# working.net
KiCad netlist of a schematic drawn in EAGLE
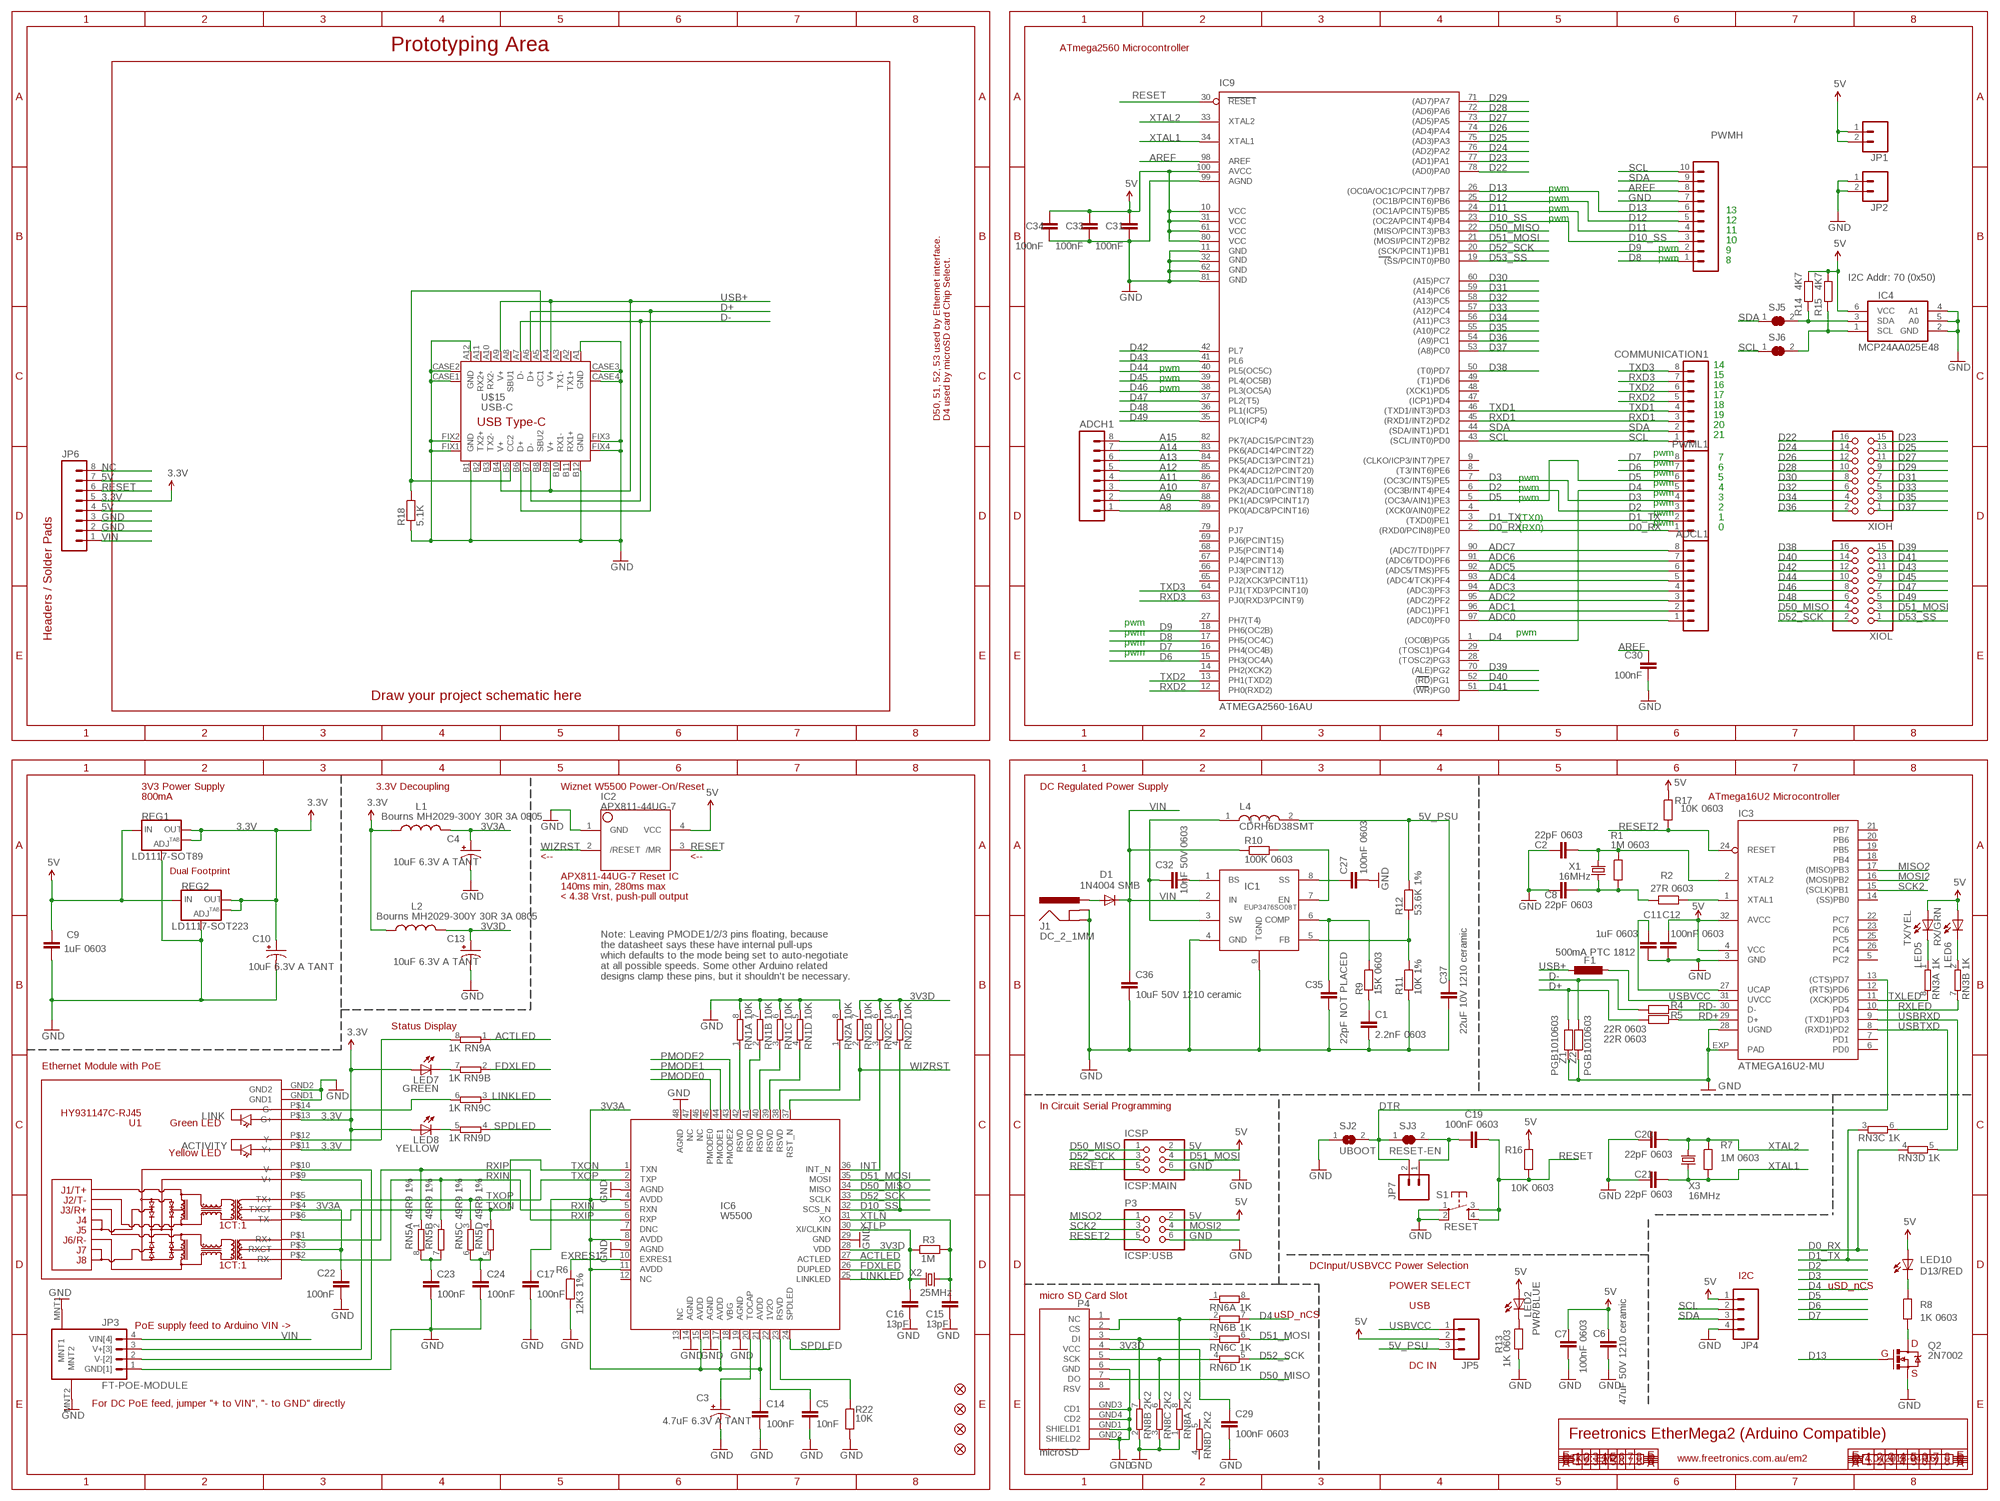
[diagram p0: schematic, sheet 1]

(export (version "E")
  (design (tool "Eeschema 10.0.6"))
  (components
    (comp (ref "ADCH1")
      (value "M08STD")
      (footprint "eagle-import:1X08")
      (libsource (lib "eagle-import") (part "M08STD"))
    )
    (comp (ref "ADCL1")
      (value "M08STD")
      (footprint "eagle-import:1X08")
      (libsource (lib "eagle-import") (part "M08STD"))
    )
    (comp (ref "C1")
      (value "2.2nF 0603")
      (footprint "eagle-import:0603")
      (libsource (lib "eagle-import") (part "freetronics-marc_CAP0603"))
    )
    (comp (ref "C2")
      (value "22pF 0603")
      (footprint "eagle-import:0603")
      (libsource (lib "eagle-import") (part "freetronics-marc_CAP0603"))
    )
    (comp (ref "C3")
      (value "4.7uF 6.3V A TANT")
      (footprint "eagle-import:EIA3216")
      (libsource (lib "eagle-import") (part "CAP_POL1206"))
    )
    (comp (ref "C4")
      (value "10uF 6.3V A TANT")
      (footprint "eagle-import:EIA3216")
      (libsource (lib "eagle-import") (part "CAP_POL1206"))
    )
    (comp (ref "C5")
      (value "10nF")
      (footprint "eagle-import:0603")
      (libsource (lib "eagle-import") (part "CAP0603"))
    )
    (comp (ref "C6")
      (value "47uF 50V 1210 ceramic")
      (footprint "eagle-import:C1210")
      (libsource (lib "eagle-import") (part "C-EUC1210"))
    )
    (comp (ref "C7")
      (value "100nF 0603")
      (footprint "eagle-import:0603")
      (libsource (lib "eagle-import") (part "freetronics-marc_CAP0603"))
    )
    (comp (ref "C8")
      (value "22pF 0603")
      (footprint "eagle-import:0603")
      (libsource (lib "eagle-import") (part "freetronics-marc_CAP0603"))
    )
    (comp (ref "C9")
      (value "1uF 0603")
      (footprint "eagle-import:0603")
      (libsource (lib "eagle-import") (part "freetronics-marc_CAP0603"))
    )
    (comp (ref "C10")
      (value "10uF 6.3V A TANT")
      (footprint "eagle-import:EIA3216")
      (libsource (lib "eagle-import") (part "CAP_POL1206"))
    )
    (comp (ref "C11")
      (value "1uF 0603")
      (footprint "eagle-import:0603")
      (libsource (lib "eagle-import") (part "freetronics-master-v1_CAP0603"))
    )
    (comp (ref "C12")
      (value "100nF 0603")
      (footprint "eagle-import:0603")
      (libsource (lib "eagle-import") (part "freetronics-marc_CAP0603"))
    )
    (comp (ref "C13")
      (value "10uF 6.3V A TANT")
      (footprint "eagle-import:EIA3216")
      (libsource (lib "eagle-import") (part "CAP_POL1206"))
    )
    (comp (ref "C14")
      (value "100nF")
      (footprint "eagle-import:0603")
      (libsource (lib "eagle-import") (part "CAP0603"))
    )
    (comp (ref "C15")
      (value "13pF")
      (footprint "eagle-import:0603")
      (libsource (lib "eagle-import") (part "freetronics-marc_CAP0603"))
    )
    (comp (ref "C16")
      (value "13pF")
      (footprint "eagle-import:0603")
      (libsource (lib "eagle-import") (part "freetronics-marc_CAP0603"))
    )
    (comp (ref "C17")
      (value "100nF")
      (footprint "eagle-import:0603")
      (libsource (lib "eagle-import") (part "CAP0603"))
    )
    (comp (ref "C19")
      (value "100nF 0603")
      (footprint "eagle-import:0603")
      (libsource (lib "eagle-import") (part "freetronics-marc_CAP0603"))
    )
    (comp (ref "C20")
      (value "22pF 0603")
      (footprint "eagle-import:0603")
      (libsource (lib "eagle-import") (part "freetronics-marc_CAP0603"))
    )
    (comp (ref "C21")
      (value "22pF 0603")
      (footprint "eagle-import:0603")
      (libsource (lib "eagle-import") (part "freetronics-marc_CAP0603"))
    )
    (comp (ref "C22")
      (value "100nF")
      (footprint "eagle-import:0603")
      (libsource (lib "eagle-import") (part "freetronics-marc_CAP0603"))
    )
    (comp (ref "C23")
      (value "100nF")
      (footprint "eagle-import:0603")
      (libsource (lib "eagle-import") (part "freetronics-marc_CAP0603"))
    )
    (comp (ref "C24")
      (value "100nF")
      (footprint "eagle-import:0603")
      (libsource (lib "eagle-import") (part "freetronics-marc_CAP0603"))
    )
    (comp (ref "C27")
      (value "100nF 0603")
      (footprint "eagle-import:0603")
      (libsource (lib "eagle-import") (part "freetronics-marc_CAP0603"))
    )
    (comp (ref "C29")
      (value "100nF 0603")
      (footprint "eagle-import:0603")
      (libsource (lib "eagle-import") (part "freetronics-marc_CAP0603"))
    )
    (comp (ref "C30")
      (value "100nF")
      (footprint "eagle-import:0603")
      (libsource (lib "eagle-import") (part "freetronics-marc_CAP0603"))
    )
    (comp (ref "C31")
      (value "100nF")
      (footprint "eagle-import:0603")
      (libsource (lib "eagle-import") (part "freetronics-marc_CAP0603"))
    )
    (comp (ref "C32")
      (value "10nF 50V 0603")
      (footprint "eagle-import:0603")
      (libsource (lib "eagle-import") (part "freetronics-marc_CAP0603"))
    )
    (comp (ref "C33")
      (value "100nF")
      (footprint "eagle-import:0603")
      (libsource (lib "eagle-import") (part "freetronics-marc_CAP0603"))
    )
    (comp (ref "C34")
      (value "100nF")
      (footprint "eagle-import:0603")
      (libsource (lib "eagle-import") (part "freetronics-marc_CAP0603"))
    )
    (comp (ref "C35")
      (value "22pF NOT PLACED")
      (footprint "eagle-import:0603")
      (libsource (lib "eagle-import") (part "freetronics-marc_CAP0603"))
    )
    (comp (ref "C36")
      (value "10uF 50V 1210 ceramic")
      (footprint "eagle-import:C1210")
      (libsource (lib "eagle-import") (part "C-EUC1210"))
    )
    (comp (ref "C37")
      (value "22uF 10V 1210 ceramic")
      (footprint "eagle-import:C1210")
      (libsource (lib "eagle-import") (part "C-EUC1210"))
    )
    (comp (ref "COMMUNICATION1")
      (value "M08STD")
      (footprint "eagle-import:1X08")
      (libsource (lib "eagle-import") (part "M08STD"))
    )
    (comp (ref "D1")
      (value "1N4004 SMB")
      (footprint "eagle-import:SMB-DIODE")
      (libsource (lib "eagle-import") (part "DIODESMB"))
    )
    (comp (ref "F1")
      (value "500mA PTC 1812")
      (footprint "eagle-import:L1812")
      (libsource (lib "eagle-import") (part "L-EUL1812"))
    )
    (comp (ref "FID1")
      (value "FIDUCIAL1X2.5")
      (footprint "eagle-import:FIDUCIAL-1X2.5")
      (libsource (lib "eagle-import") (part "FIDUCIAL1X2.5"))
    )
    (comp (ref "FID2")
      (value "FIDUCIAL1X2.5")
      (footprint "eagle-import:FIDUCIAL-1X2.5")
      (libsource (lib "eagle-import") (part "FIDUCIAL1X2.5"))
    )
    (comp (ref "FID3")
      (value "FIDUCIAL1X2.5")
      (footprint "eagle-import:FIDUCIAL-1X2.5")
      (libsource (lib "eagle-import") (part "FIDUCIAL1X2.5"))
    )
    (comp (ref "FID4")
      (value "FIDUCIAL1X2.5")
      (footprint "eagle-import:FIDUCIAL-1X2.5")
      (libsource (lib "eagle-import") (part "FIDUCIAL1X2.5"))
    )
    (comp (ref "IC1")
      (value "EUP3476SO08T")
      (footprint "eagle-import:SO08T")
      (libsource (lib "eagle-import") (part "EUP3476SO08T"))
    )
    (comp (ref "IC2")
      (value "APX811-44UG-7")
      (footprint "eagle-import:SOT143-R")
      (libsource (lib "eagle-import") (part "APX81X-RESET-IC"))
    )
    (comp (ref "IC3")
      (value "ATMEGA16U2-MU")
      (footprint "eagle-import:ATMEL_QFN32")
      (libsource (lib "eagle-import") (part "ATMEL_ATMEGA8U2-MUQFN"))
    )
    (comp (ref "IC4")
      (value "MCP24AA025E48")
      (footprint "eagle-import:SOT23-6")
      (libsource (lib "eagle-import") (part "MCP24AA025E48"))
    )
    (comp (ref "IC6")
      (value "W5500")
      (footprint "eagle-import:W5500")
      (libsource (lib "eagle-import") (part "W5500"))
    )
    (comp (ref "IC9")
      (value "ATMEGA2560-16AU")
      (footprint "eagle-import:TQFP100")
      (libsource (lib "eagle-import") (part "ATMEGAAU1280-16"))
    )
    (comp (ref "ICSP")
      (value "ICSP:MAIN")
      (footprint "eagle-import:2X03")
      (libsource (lib "eagle-import") (part "PINHD-2X3"))
    )
    (comp (ref "J1")
      (value "DC_2_1MM")
      (footprint "eagle-import:POWER_JACK_PTH_SLOTS")
      (libsource (lib "eagle-import") (part "POWER_JACKPTH_SLOTS"))
    )
    (comp (ref "JP1")
      (value "M02PTH")
      (footprint "eagle-import:1X02")
      (libsource (lib "eagle-import") (part "M02PTH"))
    )
    (comp (ref "JP2")
      (value "M02PTH")
      (footprint "eagle-import:1X02")
      (libsource (lib "eagle-import") (part "M02PTH"))
    )
    (comp (ref "JP3")
      (value "FT-POE-MODULE")
      (footprint "eagle-import:FT-POE-MODULE-CLEAN")
      (libsource (lib "eagle-import") (part "FT-POE-MODULE2"))
    )
    (comp (ref "JP4")
      (value "M04PTH")
      (footprint "eagle-import:1X04")
      (libsource (lib "eagle-import") (part "M04PTH"))
    )
    (comp (ref "JP5")
      (value "M03PTH")
      (footprint "eagle-import:1X03")
      (libsource (lib "eagle-import") (part "M03PTH"))
    )
    (comp (ref "JP6")
      (value "M08STD")
      (footprint "eagle-import:1X08")
      (libsource (lib "eagle-import") (part "M08STD"))
    )
    (comp (ref "JP7")
      (value "M02PTH")
      (footprint "eagle-import:1X02")
      (libsource (lib "eagle-import") (part "freetronics-master-v1.1_M02PTH"))
    )
    (comp (ref "L1")
      (value "Bourns MH2029-300Y 30R 3A 0805")
      (footprint "eagle-import:L2012C")
      (libsource (lib "eagle-import") (part "L-USL2012C"))
    )
    (comp (ref "L2")
      (value "Bourns MH2029-300Y 30R 3A 0805")
      (footprint "eagle-import:L2012C")
      (libsource (lib "eagle-import") (part "L-USL2012C"))
    )
    (comp (ref "L4")
      (value "CDRH6D38SMT")
      (footprint "eagle-import:CDRH")
      (libsource (lib "eagle-import") (part "CDRH6D38SMT"))
    )
    (comp (ref "LED2")
      (value "PWR/BLUE")
      (footprint "eagle-import:LED-0603")
      (libsource (lib "eagle-import") (part "LED0603"))
    )
    (comp (ref "LED5")
      (value "TX/YEL")
      (footprint "eagle-import:LED-0603")
      (libsource (lib "eagle-import") (part "LED0603"))
    )
    (comp (ref "LED6")
      (value "RX/GRN")
      (footprint "eagle-import:LED-0603")
      (libsource (lib "eagle-import") (part "LED0603"))
    )
    (comp (ref "LED7")
      (value "GREEN")
      (footprint "eagle-import:LED-0603")
      (libsource (lib "eagle-import") (part "LED0603"))
    )
    (comp (ref "LED8")
      (value "YELLOW")
      (footprint "eagle-import:LED-0603")
      (libsource (lib "eagle-import") (part "LED0603"))
    )
    (comp (ref "LED10")
      (value "D13/RED")
      (footprint "eagle-import:LED-0603")
      (libsource (lib "eagle-import") (part "LED0603"))
    )
    (comp (ref "P3")
      (value "ICSP:USB")
      (footprint "eagle-import:2X03")
      (libsource (lib "eagle-import") (part "PINHD-2X3"))
    )
    (comp (ref "P4")
      (value "microSD")
      (footprint "eagle-import:MOLEX-SD-500901-003")
      (libsource (lib "eagle-import") (part "USD-SOCKETHINGE"))
    )
    (comp (ref "PWMH")
      (value "M100.1")
      (footprint "eagle-import:1X10")
      (libsource (lib "eagle-import") (part "M100.1"))
    )
    (comp (ref "PWML1")
      (value "M08STD")
      (footprint "eagle-import:1X08")
      (libsource (lib "eagle-import") (part "M08STD"))
    )
    (comp (ref "Q2")
      (value "2N7002")
      (footprint "eagle-import:SOT23-3")
      (libsource (lib "eagle-import") (part "MOSFET-NCHANNELSMD"))
    )
    (comp (ref "R1")
      (value "1M 0603")
      (footprint "eagle-import:0603")
      (libsource (lib "eagle-import") (part "freetronics-marc_RESISTOR0603"))
    )
    (comp (ref "R2")
      (value "27R 0603")
      (footprint "eagle-import:0603")
      (libsource (lib "eagle-import") (part "freetronics-marc_RESISTOR0603"))
    )
    (comp (ref "R3")
      (value "1M")
      (footprint "eagle-import:0603")
      (libsource (lib "eagle-import") (part "freetronics-marc_RESISTOR0603"))
    )
    (comp (ref "R4")
      (value "22R 0603")
      (footprint "eagle-import:0603")
      (libsource (lib "eagle-import") (part "freetronics-marc_RESISTOR0603"))
    )
    (comp (ref "R5")
      (value "22R 0603")
      (footprint "eagle-import:0603")
      (libsource (lib "eagle-import") (part "freetronics-marc_RESISTOR0603"))
    )
    (comp (ref "R6")
      (value "12K3 1%")
      (footprint "eagle-import:0603")
      (libsource (lib "eagle-import") (part "freetronics-marc_RESISTOR0603"))
    )
    (comp (ref "R7")
      (value "1M 0603")
      (footprint "eagle-import:0603")
      (libsource (lib "eagle-import") (part "freetronics-marc_RESISTOR0603"))
    )
    (comp (ref "R8")
      (value "1K 0603")
      (footprint "eagle-import:0603")
      (libsource (lib "eagle-import") (part "freetronics-marc_RESISTOR0603"))
    )
    (comp (ref "R9")
      (value "15K 0603")
      (footprint "eagle-import:0603")
      (libsource (lib "eagle-import") (part "freetronics-original_RESISTOR0603"))
    )
    (comp (ref "R10")
      (value "100K 0603")
      (footprint "eagle-import:0603")
      (libsource (lib "eagle-import") (part "freetronics-original_RESISTOR0603"))
    )
    (comp (ref "R11")
      (value "10K 1%")
      (footprint "eagle-import:0603")
      (libsource (lib "eagle-import") (part "freetronics-original_RESISTOR0603"))
    )
    (comp (ref "R12")
      (value "53.6K 1%")
      (footprint "eagle-import:0603")
      (libsource (lib "eagle-import") (part "freetronics-original_RESISTOR0603"))
    )
    (comp (ref "R13")
      (value "1K 0603")
      (footprint "eagle-import:0603")
      (libsource (lib "eagle-import") (part "freetronics-marc_RESISTOR0603"))
    )
    (comp (ref "R14")
      (value "4K7")
      (footprint "eagle-import:0603")
      (libsource (lib "eagle-import") (part "freetronics-master-v1.1_RESISTOR0603"))
    )
    (comp (ref "R15")
      (value "4K7")
      (footprint "eagle-import:0603")
      (libsource (lib "eagle-import") (part "freetronics-master-v1.1_RESISTOR0603"))
    )
    (comp (ref "R16")
      (value "10K 0603")
      (footprint "eagle-import:0603")
      (libsource (lib "eagle-import") (part "freetronics-marc_RESISTOR0603"))
    )
    (comp (ref "R17")
      (value "10K 0603")
      (footprint "eagle-import:0603")
      (libsource (lib "eagle-import") (part "freetronics-marc_RESISTOR0603"))
    )
    (comp (ref "R18")
      (value "5.1K")
      (footprint "eagle-import:0603")
      (libsource (lib "eagle-import") (part "freetronics-original_RESISTOR0603"))
    )
    (comp (ref "R22")
      (value "10K")
      (footprint "eagle-import:0603")
      (libsource (lib "eagle-import") (part "freetronics-marc_RESISTOR0603"))
    )
    (comp (ref "REG1")
      (value "LD1117-SOT89")
      (footprint "eagle-import:SOT89")
      (libsource (lib "eagle-import") (part "V_REG_LM1117SOT89"))
    )
    (comp (ref "REG2")
      (value "LD1117-SOT223")
      (footprint "eagle-import:SOT223")
      (libsource (lib "eagle-import") (part "V_REG_LM1117SOT223"))
    )
    (comp (ref "RN1")
      (value "10K")
      (footprint "eagle-import:CAY16")
      (libsource (lib "eagle-import") (part "freetronics-master-v1.1_4R-NCAY16"))
    )
    (comp (ref "RN2")
      (value "10K")
      (footprint "eagle-import:CAY16")
      (libsource (lib "eagle-import") (part "freetronics-master-v1.1_4R-NCAY16"))
    )
    (comp (ref "RN3")
      (value "1K")
      (footprint "eagle-import:CAY16")
      (libsource (lib "eagle-import") (part "4R-NCAY16"))
    )
    (comp (ref "RN5")
      (value "49R9 1%")
      (footprint "eagle-import:CAY16")
      (libsource (lib "eagle-import") (part "4R-NCAY16"))
    )
    (comp (ref "RN6")
      (value "1K")
      (footprint "eagle-import:CAY16")
      (libsource (lib "eagle-import") (part "4R-NCAY16"))
    )
    (comp (ref "RN8")
      (value "2K2")
      (footprint "eagle-import:CAY16")
      (libsource (lib "eagle-import") (part "4R-NCAY16"))
    )
    (comp (ref "RN9")
      (value "1K")
      (footprint "eagle-import:CAY16")
      (libsource (lib "eagle-import") (part "freetronics-master-v1.1_4R-NCAY16"))
    )
    (comp (ref "S1")
      (value "RESET")
      (footprint "eagle-import:TACTILE_SWITCH_SMD")
      (libsource (lib "eagle-import") (part "TAC_SWITCHSMD"))
    )
    (comp (ref "SJ2")
      (value "UBOOT")
      (footprint "eagle-import:SJ")
      (libsource (lib "eagle-import") (part "SJ"))
    )
    (comp (ref "SJ3")
      (value "RESET-EN")
      (footprint "eagle-import:SJC")
      (libsource (lib "eagle-import") (part "SJCN"))
    )
    (comp (ref "SJ5")
      (value "SJCN")
      (footprint "eagle-import:SJC")
      (libsource (lib "eagle-import") (part "SJCN"))
    )
    (comp (ref "SJ6")
      (value "SJCN")
      (footprint "eagle-import:SJC")
      (libsource (lib "eagle-import") (part "SJCN"))
    )
    (comp (ref "U$15")
      (value "USB-C")
      (footprint "eagle-import:USB-C-U52A")
      (libsource (lib "eagle-import") (part "USB-C"))
    )
    (comp (ref "U1")
      (value "HY931147C-RJ45")
      (footprint "eagle-import:HY931147C")
      (libsource (lib "eagle-import") (part "HY931147C-RJ45"))
    )
    (comp (ref "X1")
      (value "16MHz")
      (footprint "eagle-import:HC49U-V")
      (libsource (lib "eagle-import") (part "CRYSTALHC49UV"))
    )
    (comp (ref "X2")
      (value "25MHz")
      (footprint "eagle-import:HC49U-V")
      (libsource (lib "eagle-import") (part "CRYSTALHC49UV"))
    )
    (comp (ref "X3")
      (value "16MHz")
      (footprint "eagle-import:HC49U-V")
      (libsource (lib "eagle-import") (part "CRYSTALHC49UV"))
    )
    (comp (ref "XIOH")
      (value "PINHD-2X8")
      (footprint "eagle-import:2X08")
      (libsource (lib "eagle-import") (part "PINHD-2X8"))
    )
    (comp (ref "XIOL")
      (value "PINHD-2X8")
      (footprint "eagle-import:2X08")
      (libsource (lib "eagle-import") (part "PINHD-2X8"))
    )
    (comp (ref "Z1")
      (value "PGB1010603")
      (footprint "eagle-import:0603")
      (libsource (lib "eagle-import") (part "RESISTOR0603"))
    )
    (comp (ref "Z2")
      (value "PGB1010603")
      (footprint "eagle-import:0603")
      (libsource (lib "eagle-import") (part "RESISTOR0603"))
    )
  )
  (nets
    (net (code "1") (name "/3V3A") (class "Default")
      (node (ref "C14") (pin "1") (pinfunction "1_1") (pintype "passive"))
      (node (ref "C17") (pin "1") (pinfunction "1_1") (pintype "passive"))
      (node (ref "C22") (pin "1") (pinfunction "1_1") (pintype "passive"))
      (node (ref "C4") (pin "A") (pinfunction "+_A") (pintype "passive"))
      (node (ref "IC6") (pin "11") (pinfunction "AVDD_11") (pintype "passive"))
      (node (ref "IC6") (pin "15") (pinfunction "AVDD_15") (pintype "passive"))
      (node (ref "IC6") (pin "17") (pinfunction "AVDD_17") (pintype "passive"))
      (node (ref "IC6") (pin "21") (pinfunction "AVDD_21") (pintype "passive"))
      (node (ref "IC6") (pin "4") (pinfunction "AVDD_4") (pintype "passive"))
      (node (ref "IC6") (pin "8") (pinfunction "AVDD_8") (pintype "passive"))
      (node (ref "L1") (pin "2") (pinfunction "2_2") (pintype "passive"))
      (node (ref "U1") (pin "P$3") (pinfunction "RXCT_P$3") (pintype "bidirectional"))
      (node (ref "U1") (pin "P$4") (pinfunction "TXCT_P$4") (pintype "bidirectional"))
    )
    (net (code "2") (name "/3V3D") (class "Default")
      (node (ref "C13") (pin "A") (pinfunction "+_A") (pintype "passive"))
      (node (ref "C29") (pin "1") (pinfunction "1_1") (pintype "passive"))
      (node (ref "IC6") (pin "28") (pinfunction "VDD_28") (pintype "passive"))
      (node (ref "L2") (pin "2") (pinfunction "2_2") (pintype "passive"))
      (node (ref "P4") (pin "4") (pinfunction "VCC_4") (pintype "bidirectional"))
      (node (ref "RN2") (pin "5") (pinfunction "2_5") (pintype "passive"))
      (node (ref "RN2") (pin "6") (pinfunction "2_6") (pintype "passive"))
      (node (ref "RN2") (pin "7") (pinfunction "2_7") (pintype "passive"))
    )
    (net (code "3") (name "/5V_PSU") (class "Default")
      (node (ref "C37") (pin "1") (pinfunction "1_1") (pintype "passive"))
      (node (ref "JP5") (pin "3") (pinfunction "3_3") (pintype "passive"))
      (node (ref "L4") (pin "2") (pinfunction "2_2") (pintype "bidirectional"))
      (node (ref "R12") (pin "2") (pinfunction "2_2") (pintype "passive"))
    )
    (net (code "4") (name "/A8") (class "Default")
      (node (ref "ADCH1") (pin "1") (pinfunction "1_1") (pintype "passive"))
      (node (ref "IC9") (pin "89") (pinfunction "PK0(ADC8/PCINT16)_89") (pintype "bidirectional"))
    )
    (net (code "5") (name "/A9") (class "Default")
      (node (ref "ADCH1") (pin "2") (pinfunction "2_2") (pintype "passive"))
      (node (ref "IC9") (pin "88") (pinfunction "PK1(ADC9/PCINT17)_88") (pintype "bidirectional"))
    )
    (net (code "6") (name "/A10") (class "Default")
      (node (ref "ADCH1") (pin "3") (pinfunction "3_3") (pintype "passive"))
      (node (ref "IC9") (pin "87") (pinfunction "PK2(ADC10/PCINT18)_87") (pintype "bidirectional"))
    )
    (net (code "7") (name "/A11") (class "Default")
      (node (ref "ADCH1") (pin "4") (pinfunction "4_4") (pintype "passive"))
      (node (ref "IC9") (pin "86") (pinfunction "PK3(ADC11/PCINT19)_86") (pintype "bidirectional"))
    )
    (net (code "8") (name "/A12") (class "Default")
      (node (ref "ADCH1") (pin "5") (pinfunction "5_5") (pintype "passive"))
      (node (ref "IC9") (pin "85") (pinfunction "PK4(ADC12/PCINT20)_85") (pintype "bidirectional"))
    )
    (net (code "9") (name "/A13") (class "Default")
      (node (ref "ADCH1") (pin "6") (pinfunction "6_6") (pintype "passive"))
      (node (ref "IC9") (pin "84") (pinfunction "PK5(ADC13/PCINT21)_84") (pintype "bidirectional"))
    )
    (net (code "10") (name "/A14") (class "Default")
      (node (ref "ADCH1") (pin "7") (pinfunction "7_7") (pintype "passive"))
      (node (ref "IC9") (pin "83") (pinfunction "PK6(ADC14/PCINT22)_83") (pintype "bidirectional"))
    )
    (net (code "11") (name "/A15") (class "Default")
      (node (ref "ADCH1") (pin "8") (pinfunction "8_8") (pintype "passive"))
      (node (ref "IC9") (pin "82") (pinfunction "PK7(ADC15/PCINT23)_82") (pintype "bidirectional"))
    )
    (net (code "12") (name "/ACTLED") (class "Default")
      (node (ref "IC6") (pin "27") (pinfunction "ACTLED_27") (pintype "passive"))
      (node (ref "RN9") (pin "1") (pinfunction "1_1") (pintype "passive"))
    )
    (net (code "13") (name "/ADC0") (class "Default")
      (node (ref "ADCL1") (pin "1") (pinfunction "1_1") (pintype "passive"))
      (node (ref "IC9") (pin "97") (pinfunction "(ADC0)PF0_97") (pintype "bidirectional"))
    )
    (net (code "14") (name "/ADC1") (class "Default")
      (node (ref "ADCL1") (pin "2") (pinfunction "2_2") (pintype "passive"))
      (node (ref "IC9") (pin "96") (pinfunction "(ADC1)PF1_96") (pintype "bidirectional"))
    )
    (net (code "15") (name "/ADC2") (class "Default")
      (node (ref "ADCL1") (pin "3") (pinfunction "3_3") (pintype "passive"))
      (node (ref "IC9") (pin "95") (pinfunction "(ADC2)PF2_95") (pintype "bidirectional"))
    )
    (net (code "16") (name "/ADC3") (class "Default")
      (node (ref "ADCL1") (pin "4") (pinfunction "4_4") (pintype "passive"))
      (node (ref "IC9") (pin "94") (pinfunction "(ADC3)PF3_94") (pintype "bidirectional"))
    )
    (net (code "17") (name "/ADC4") (class "Default")
      (node (ref "ADCL1") (pin "5") (pinfunction "5_5") (pintype "passive"))
      (node (ref "IC9") (pin "93") (pinfunction "(ADC4/TCK)PF4_93") (pintype "bidirectional"))
    )
    (net (code "18") (name "/ADC5") (class "Default")
      (node (ref "ADCL1") (pin "6") (pinfunction "6_6") (pintype "passive"))
      (node (ref "IC9") (pin "92") (pinfunction "(ADC5/TMS)PF5_92") (pintype "bidirectional"))
    )
    (net (code "19") (name "/ADC6") (class "Default")
      (node (ref "ADCL1") (pin "7") (pinfunction "7_7") (pintype "passive"))
      (node (ref "IC9") (pin "91") (pinfunction "(ADC6/TDO)PF6_91") (pintype "bidirectional"))
    )
    (net (code "20") (name "/ADC7") (class "Default")
      (node (ref "ADCL1") (pin "8") (pinfunction "8_8") (pintype "passive"))
      (node (ref "IC9") (pin "90") (pinfunction "(ADC7/TDI)PF7_90") (pintype "bidirectional"))
    )
    (net (code "21") (name "/AREF") (class "Default")
      (node (ref "C30") (pin "1") (pinfunction "1_1") (pintype "passive"))
      (node (ref "IC9") (pin "98") (pinfunction "AREF_98") (pintype "bidirectional"))
      (node (ref "PWMH") (pin "8") (pinfunction "8_8") (pintype "passive"))
    )
    (net (code "22") (name "/D+") (class "Default")
      (node (ref "R5") (pin "2") (pinfunction "2_2") (pintype "passive"))
      (node (ref "U$15") (pin "A6") (pinfunction "D+_A6") (pintype "bidirectional"))
      (node (ref "U$15") (pin "B6") (pinfunction "D+_B6") (pintype "bidirectional"))
      (node (ref "Z1") (pin "1") (pinfunction "1_1") (pintype "passive"))
    )
    (net (code "23") (name "/D-") (class "Default")
      (node (ref "R4") (pin "2") (pinfunction "2_2") (pintype "passive"))
      (node (ref "U$15") (pin "A7") (pinfunction "D-_A7") (pintype "bidirectional"))
      (node (ref "U$15") (pin "B7") (pinfunction "D-_B7") (pintype "bidirectional"))
      (node (ref "Z2") (pin "1") (pinfunction "1_1") (pintype "passive"))
    )
    (net (code "24") (name "/D0_RX") (class "Default")
      (node (ref "IC9") (pin "2") (pinfunction "(RXD0/PCIN8)PE0_2") (pintype "bidirectional"))
      (node (ref "PWML1") (pin "1") (pinfunction "1_1") (pintype "passive"))
      (node (ref "RN3") (pin "4") (pinfunction "1_4") (pintype "passive"))
    )
    (net (code "25") (name "/D1_TX") (class "Default")
      (node (ref "IC9") (pin "3") (pinfunction "(TXD0)PE1_3") (pintype "bidirectional"))
      (node (ref "PWML1") (pin "2") (pinfunction "2_2") (pintype "passive"))
      (node (ref "RN3") (pin "3") (pinfunction "1_3") (pintype "passive"))
    )
    (net (code "26") (name "/D2") (class "Default")
      (node (ref "IC9") (pin "6") (pinfunction "(OC3B/INT4)PE4_6") (pintype "bidirectional"))
      (node (ref "PWML1") (pin "3") (pinfunction "3_3") (pintype "passive"))
    )
    (net (code "27") (name "/D3") (class "Default")
      (node (ref "IC9") (pin "7") (pinfunction "(OC3C/INT5)PE5_7") (pintype "bidirectional"))
      (node (ref "PWML1") (pin "4") (pinfunction "4_4") (pintype "passive"))
    )
    (net (code "28") (name "/D4") (class "Default")
      (node (ref "IC9") (pin "1") (pinfunction "(OC0B)PG5_1") (pintype "bidirectional"))
      (node (ref "PWML1") (pin "5") (pinfunction "5_5") (pintype "passive"))
      (node (ref "RN6") (pin "7") (pinfunction "2_7") (pintype "passive"))
    )
    (net (code "29") (name "/D5") (class "Default")
      (node (ref "IC9") (pin "5") (pinfunction "(OC3A/AIN1)PE3_5") (pintype "bidirectional"))
      (node (ref "PWML1") (pin "6") (pinfunction "6_6") (pintype "passive"))
    )
    (net (code "30") (name "/D6") (class "Default")
      (node (ref "IC9") (pin "15") (pinfunction "PH3(OC4A)_15") (pintype "bidirectional"))
      (node (ref "PWML1") (pin "7") (pinfunction "7_7") (pintype "passive"))
    )
    (net (code "31") (name "/D7") (class "Default")
      (node (ref "IC9") (pin "16") (pinfunction "PH4(OC4B)_16") (pintype "bidirectional"))
      (node (ref "PWML1") (pin "8") (pinfunction "8_8") (pintype "passive"))
    )
    (net (code "32") (name "/D8") (class "Default")
      (node (ref "IC9") (pin "17") (pinfunction "PH5(OC4C)_17") (pintype "bidirectional"))
      (node (ref "PWMH") (pin "1") (pinfunction "1_1") (pintype "passive"))
    )
    (net (code "33") (name "/D9") (class "Default")
      (node (ref "IC9") (pin "18") (pinfunction "PH6(OC2B)_18") (pintype "bidirectional"))
      (node (ref "PWMH") (pin "2") (pinfunction "2_2") (pintype "passive"))
    )
    (net (code "34") (name "/D10_SS") (class "Default")
      (node (ref "IC6") (pin "32") (pinfunction "SCS_N_32") (pintype "passive"))
      (node (ref "IC9") (pin "23") (pinfunction "(OC2A/PCINT4)PB4_23") (pintype "bidirectional"))
      (node (ref "PWMH") (pin "3") (pinfunction "3_3") (pintype "passive"))
      (node (ref "RN2") (pin "4") (pinfunction "1_4") (pintype "passive"))
    )
    (net (code "35") (name "/D11") (class "Default")
      (node (ref "IC9") (pin "24") (pinfunction "(OC1A/PCINT5)PB5_24") (pintype "bidirectional"))
      (node (ref "PWMH") (pin "4") (pinfunction "4_4") (pintype "passive"))
    )
    (net (code "36") (name "/D12") (class "Default")
      (node (ref "IC9") (pin "25") (pinfunction "(OC1B/PCINT6)PB6_25") (pintype "bidirectional"))
      (node (ref "PWMH") (pin "5") (pinfunction "5_5") (pintype "passive"))
    )
    (net (code "37") (name "/D13") (class "Default")
      (node (ref "IC9") (pin "26") (pinfunction "(OC0A/OC1C/PCINT7)PB7_26") (pintype "bidirectional"))
      (node (ref "PWMH") (pin "6") (pinfunction "6_6") (pintype "passive"))
      (node (ref "Q2") (pin "1") (pinfunction "G_1") (pintype "passive"))
    )
    (net (code "38") (name "/D22") (class "Default")
      (node (ref "IC9") (pin "78") (pinfunction "(AD0)PA0_78") (pintype "bidirectional"))
      (node (ref "XIOH") (pin "16") (pinfunction "16_16") (pintype "passive"))
    )
    (net (code "39") (name "/D23") (class "Default")
      (node (ref "IC9") (pin "77") (pinfunction "(AD1)PA1_77") (pintype "bidirectional"))
      (node (ref "XIOH") (pin "15") (pinfunction "15_15") (pintype "passive"))
    )
    (net (code "40") (name "/D24") (class "Default")
      (node (ref "IC9") (pin "76") (pinfunction "(AD2)PA2_76") (pintype "bidirectional"))
      (node (ref "XIOH") (pin "14") (pinfunction "14_14") (pintype "passive"))
    )
    (net (code "41") (name "/D25") (class "Default")
      (node (ref "IC9") (pin "75") (pinfunction "(AD3)PA3_75") (pintype "bidirectional"))
      (node (ref "XIOH") (pin "13") (pinfunction "13_13") (pintype "passive"))
    )
    (net (code "42") (name "/D26") (class "Default")
      (node (ref "IC9") (pin "74") (pinfunction "(AD4)PA4_74") (pintype "bidirectional"))
      (node (ref "XIOH") (pin "12") (pinfunction "12_12") (pintype "passive"))
    )
    (net (code "43") (name "/D27") (class "Default")
      (node (ref "IC9") (pin "73") (pinfunction "(AD5)PA5_73") (pintype "bidirectional"))
      (node (ref "XIOH") (pin "11") (pinfunction "11_11") (pintype "passive"))
    )
    (net (code "44") (name "/D28") (class "Default")
      (node (ref "IC9") (pin "72") (pinfunction "(AD6)PA6_72") (pintype "bidirectional"))
      (node (ref "XIOH") (pin "10") (pinfunction "10_10") (pintype "passive"))
    )
    (net (code "45") (name "/D29") (class "Default")
      (node (ref "IC9") (pin "71") (pinfunction "(AD7)PA7_71") (pintype "bidirectional"))
      (node (ref "XIOH") (pin "9") (pinfunction "9_9") (pintype "passive"))
    )
    (net (code "46") (name "/D30") (class "Default")
      (node (ref "IC9") (pin "60") (pinfunction "(A15)PC7_60") (pintype "bidirectional"))
      (node (ref "XIOH") (pin "8") (pinfunction "8_8") (pintype "passive"))
    )
    (net (code "47") (name "/D31") (class "Default")
      (node (ref "IC9") (pin "59") (pinfunction "(A14)PC6_59") (pintype "bidirectional"))
      (node (ref "XIOH") (pin "7") (pinfunction "7_7") (pintype "passive"))
    )
    (net (code "48") (name "/D32") (class "Default")
      (node (ref "IC9") (pin "58") (pinfunction "(A13)PC5_58") (pintype "bidirectional"))
      (node (ref "XIOH") (pin "6") (pinfunction "6_6") (pintype "passive"))
    )
    (net (code "49") (name "/D33") (class "Default")
      (node (ref "IC9") (pin "57") (pinfunction "(A12)PC4_57") (pintype "bidirectional"))
      (node (ref "XIOH") (pin "5") (pinfunction "5_5") (pintype "passive"))
    )
    (net (code "50") (name "/D34") (class "Default")
      (node (ref "IC9") (pin "56") (pinfunction "(A11)PC3_56") (pintype "bidirectional"))
      (node (ref "XIOH") (pin "4") (pinfunction "4_4") (pintype "passive"))
    )
    (net (code "51") (name "/D35") (class "Default")
      (node (ref "IC9") (pin "55") (pinfunction "(A10)PC2_55") (pintype "bidirectional"))
      (node (ref "XIOH") (pin "3") (pinfunction "3_3") (pintype "passive"))
    )
    (net (code "52") (name "/D36") (class "Default")
      (node (ref "IC9") (pin "54") (pinfunction "(A9)PC1_54") (pintype "bidirectional"))
      (node (ref "XIOH") (pin "2") (pinfunction "2_2") (pintype "passive"))
    )
    (net (code "53") (name "/D37") (class "Default")
      (node (ref "IC9") (pin "53") (pinfunction "(A8)PC0_53") (pintype "bidirectional"))
      (node (ref "XIOH") (pin "1") (pinfunction "1_1") (pintype "passive"))
    )
    (net (code "54") (name "/D38") (class "Default")
      (node (ref "IC9") (pin "50") (pinfunction "(T0)PD7_50") (pintype "bidirectional"))
      (node (ref "XIOL") (pin "16") (pinfunction "16_16") (pintype "passive"))
    )
    (net (code "55") (name "/D39") (class "Default")
      (node (ref "IC9") (pin "70") (pinfunction "(ALE)PG2_70") (pintype "bidirectional"))
      (node (ref "XIOL") (pin "15") (pinfunction "15_15") (pintype "passive"))
    )
    (net (code "56") (name "/D40") (class "Default")
      (node (ref "IC9") (pin "52") (pinfunction "(RD)PG1_52") (pintype "bidirectional"))
      (node (ref "XIOL") (pin "14") (pinfunction "14_14") (pintype "passive"))
    )
    (net (code "57") (name "/D41") (class "Default")
      (node (ref "IC9") (pin "51") (pinfunction "(WR)PG0_51") (pintype "bidirectional"))
      (node (ref "XIOL") (pin "13") (pinfunction "13_13") (pintype "passive"))
    )
    (net (code "58") (name "/D42") (class "Default")
      (node (ref "IC9") (pin "42") (pinfunction "PL7_42") (pintype "bidirectional"))
      (node (ref "XIOL") (pin "12") (pinfunction "12_12") (pintype "passive"))
    )
    (net (code "59") (name "/D43") (class "Default")
      (node (ref "IC9") (pin "41") (pinfunction "PL6_41") (pintype "bidirectional"))
      (node (ref "XIOL") (pin "11") (pinfunction "11_11") (pintype "passive"))
    )
    (net (code "60") (name "/D44") (class "Default")
      (node (ref "IC9") (pin "40") (pinfunction "PL5(OC5C)_40") (pintype "bidirectional"))
      (node (ref "XIOL") (pin "10") (pinfunction "10_10") (pintype "passive"))
    )
    (net (code "61") (name "/D45") (class "Default")
      (node (ref "IC9") (pin "39") (pinfunction "PL4(OC5B)_39") (pintype "bidirectional"))
      (node (ref "XIOL") (pin "9") (pinfunction "9_9") (pintype "passive"))
    )
    (net (code "62") (name "/D46") (class "Default")
      (node (ref "IC9") (pin "38") (pinfunction "PL3(OC5A)_38") (pintype "bidirectional"))
      (node (ref "XIOL") (pin "8") (pinfunction "8_8") (pintype "passive"))
    )
    (net (code "63") (name "/D47") (class "Default")
      (node (ref "IC9") (pin "37") (pinfunction "PL2(T5)_37") (pintype "bidirectional"))
      (node (ref "XIOL") (pin "7") (pinfunction "7_7") (pintype "passive"))
    )
    (net (code "64") (name "/D48") (class "Default")
      (node (ref "IC9") (pin "36") (pinfunction "PL1(ICP5)_36") (pintype "bidirectional"))
      (node (ref "XIOL") (pin "6") (pinfunction "6_6") (pintype "passive"))
    )
    (net (code "65") (name "/D49") (class "Default")
      (node (ref "IC9") (pin "35") (pinfunction "PL0(ICP4)_35") (pintype "bidirectional"))
      (node (ref "XIOL") (pin "5") (pinfunction "5_5") (pintype "passive"))
    )
    (net (code "66") (name "/D50_MISO") (class "Default")
      (node (ref "IC6") (pin "34") (pinfunction "MISO_34") (pintype "passive"))
      (node (ref "IC9") (pin "22") (pinfunction "(MISO/PCINT3)PB3_22") (pintype "bidirectional"))
      (node (ref "ICSP") (pin "1") (pinfunction "1_1") (pintype "passive"))
      (node (ref "P4") (pin "7") (pinfunction "DO_7") (pintype "bidirectional"))
      (node (ref "XIOL") (pin "4") (pinfunction "4_4") (pintype "passive"))
    )
    (net (code "67") (name "/D51_MOSI") (class "Default")
      (node (ref "IC6") (pin "35") (pinfunction "MOSI_35") (pintype "passive"))
      (node (ref "IC9") (pin "21") (pinfunction "(MOSI/PCINT2)PB2_21") (pintype "bidirectional"))
      (node (ref "ICSP") (pin "4") (pinfunction "4_4") (pintype "passive"))
      (node (ref "RN6") (pin "6") (pinfunction "2_6") (pintype "passive"))
      (node (ref "XIOL") (pin "3") (pinfunction "3_3") (pintype "passive"))
    )
    (net (code "68") (name "/D52_SCK") (class "Default")
      (node (ref "IC6") (pin "33") (pinfunction "SCLK_33") (pintype "passive"))
      (node (ref "IC9") (pin "20") (pinfunction "(SCK/PCINT1)PB1_20") (pintype "bidirectional"))
      (node (ref "ICSP") (pin "3") (pinfunction "3_3") (pintype "passive"))
      (node (ref "RN6") (pin "5") (pinfunction "2_5") (pintype "passive"))
      (node (ref "XIOL") (pin "2") (pinfunction "2_2") (pintype "passive"))
    )
    (net (code "69") (name "/D53_SS") (class "Default")
      (node (ref "IC9") (pin "19") (pinfunction "(SS/PCINT0)PB0_19") (pintype "bidirectional"))
      (node (ref "XIOL") (pin "1") (pinfunction "1_1") (pintype "passive"))
    )
    (net (code "70") (name "/DTR") (class "Default")
      (node (ref "IC3") (pin "13") (pinfunction "(CTS)PD7_13") (pintype "bidirectional"))
      (node (ref "JP7") (pin "2") (pinfunction "2_2") (pintype "passive"))
      (node (ref "SJ2") (pin "2") (pinfunction "2_2") (pintype "passive"))
      (node (ref "SJ3") (pin "1") (pinfunction "1_1") (pintype "passive"))
    )
    (net (code "71") (name "/EXRES1") (class "Default")
      (node (ref "IC6") (pin "10") (pinfunction "EXRES1_10") (pintype "passive"))
      (node (ref "R6") (pin "2") (pinfunction "2_2") (pintype "passive"))
    )
    (net (code "72") (name "/FDXLED") (class "Default")
      (node (ref "IC6") (pin "26") (pinfunction "DUPLED_26") (pintype "passive"))
      (node (ref "RN9") (pin "2") (pinfunction "1_2") (pintype "passive"))
    )
    (net (code "73") (name "/INT") (class "Default")
      (node (ref "IC6") (pin "36") (pinfunction "INT_N_36") (pintype "passive"))
      (node (ref "RN2") (pin "3") (pinfunction "1_3") (pintype "passive"))
    )
    (net (code "74") (name "/LINKLED") (class "Default")
      (node (ref "IC6") (pin "25") (pinfunction "LINKLED_25") (pintype "passive"))
      (node (ref "RN9") (pin "3") (pinfunction "1_3") (pintype "passive"))
    )
    (net (code "75") (name "/MISO2") (class "Default")
      (node (ref "IC3") (pin "17") (pinfunction "(MISO)PB3_17") (pintype "bidirectional"))
      (node (ref "P3") (pin "1") (pinfunction "1_1") (pintype "passive"))
    )
    (net (code "76") (name "/MOSI2") (class "Default")
      (node (ref "IC3") (pin "16") (pinfunction "(MOSI)PB2_16") (pintype "bidirectional"))
      (node (ref "P3") (pin "4") (pinfunction "4_4") (pintype "passive"))
    )
    (net (code "77") (name "/NC") (class "Default")
      (node (ref "JP6") (pin "8") (pinfunction "8_8") (pintype "passive"))
    )
    (net (code "78") (name "/PMODE0") (class "Default")
      (node (ref "IC6") (pin "45") (pinfunction "PMODE0_45") (pintype "passive"))
    )
    (net (code "79") (name "/PMODE1") (class "Default")
      (node (ref "IC6") (pin "44") (pinfunction "PMODE1_44") (pintype "passive"))
    )
    (net (code "80") (name "/PMODE2") (class "Default")
      (node (ref "IC6") (pin "43") (pinfunction "PMODE2_43") (pintype "passive"))
    )
    (net (code "81") (name "/RD+") (class "Default")
      (node (ref "IC3") (pin "29") (pinfunction "D+_29") (pintype "bidirectional"))
      (node (ref "R5") (pin "1") (pinfunction "1_1") (pintype "passive"))
    )
    (net (code "82") (name "/RD-") (class "Default")
      (node (ref "IC3") (pin "30") (pinfunction "D-_30") (pintype "bidirectional"))
      (node (ref "R4") (pin "1") (pinfunction "1_1") (pintype "passive"))
    )
    (net (code "83") (name "/RESET") (class "Default")
      (node (ref "C19") (pin "2") (pinfunction "2_2") (pintype "passive"))
      (node (ref "IC2") (pin "3") (pinfunction "/MR_3") (pintype "input"))
      (node (ref "IC9") (pin "30") (pinfunction "RESET_30") (pintype "input"))
      (node (ref "ICSP") (pin "5") (pinfunction "5_5") (pintype "passive"))
      (node (ref "JP6") (pin "6") (pinfunction "6_6") (pintype "passive"))
      (node (ref "R16") (pin "1") (pinfunction "1_1") (pintype "passive"))
      (node (ref "S1") (pin "3") (pinfunction "3_3") (pintype "passive"))
      (node (ref "S1") (pin "4") (pinfunction "4_4") (pintype "passive"))
    )
    (net (code "84") (name "/RESET2") (class "Default")
      (node (ref "IC3") (pin "24") (pinfunction "RESET_24") (pintype "input"))
      (node (ref "P3") (pin "5") (pinfunction "5_5") (pintype "passive"))
      (node (ref "R17") (pin "1") (pinfunction "1_1") (pintype "passive"))
    )
    (net (code "85") (name "/RXD1") (class "Default")
      (node (ref "COMMUNICATION1") (pin "3") (pinfunction "3_3") (pintype "passive"))
      (node (ref "IC9") (pin "45") (pinfunction "(RXD1/INT2)PD2_45") (pintype "bidirectional"))
    )
    (net (code "86") (name "/RXD2") (class "Default")
      (node (ref "COMMUNICATION1") (pin "5") (pinfunction "5_5") (pintype "passive"))
      (node (ref "IC9") (pin "12") (pinfunction "PH0(RXD2)_12") (pintype "bidirectional"))
    )
    (net (code "87") (name "/RXD3") (class "Default")
      (node (ref "COMMUNICATION1") (pin "7") (pinfunction "7_7") (pintype "passive"))
      (node (ref "IC9") (pin "63") (pinfunction "PJ0(RXD3/PCINT9)_63") (pintype "bidirectional"))
    )
    (net (code "88") (name "/RXIN") (class "Default")
      (node (ref "IC6") (pin "5") (pinfunction "RXN_5") (pintype "passive"))
      (node (ref "RN5") (pin "2") (pinfunction "1_2") (pintype "passive"))
      (node (ref "U1") (pin "P$2") (pinfunction "RX-_P$2") (pintype "bidirectional"))
    )
    (net (code "89") (name "/RXIP") (class "Default")
      (node (ref "IC6") (pin "6") (pinfunction "RXP_6") (pintype "passive"))
      (node (ref "RN5") (pin "1") (pinfunction "1_1") (pintype "passive"))
      (node (ref "U1") (pin "P$1") (pinfunction "RX+_P$1") (pintype "bidirectional"))
    )
    (net (code "90") (name "/RXLED") (class "Default")
      (node (ref "IC3") (pin "10") (pinfunction "PD4_10") (pintype "bidirectional"))
      (node (ref "RN3") (pin "7") (pinfunction "2_7") (pintype "passive"))
    )
    (net (code "91") (name "/SCK2") (class "Default")
      (node (ref "IC3") (pin "15") (pinfunction "(SCLK)PB1_15") (pintype "bidirectional"))
      (node (ref "P3") (pin "3") (pinfunction "3_3") (pintype "passive"))
    )
    (net (code "92") (name "/SCL") (class "Default")
      (node (ref "COMMUNICATION1") (pin "1") (pinfunction "1_1") (pintype "passive"))
      (node (ref "IC9") (pin "43") (pinfunction "(SCL/INT0)PD0_43") (pintype "bidirectional"))
      (node (ref "JP4") (pin "2") (pinfunction "2_2") (pintype "passive"))
      (node (ref "PWMH") (pin "10") (pinfunction "10_10") (pintype "passive"))
      (node (ref "SJ6") (pin "1") (pinfunction "1_1") (pintype "passive"))
    )
    (net (code "93") (name "/SDA") (class "Default")
      (node (ref "COMMUNICATION1") (pin "2") (pinfunction "2_2") (pintype "passive"))
      (node (ref "IC9") (pin "44") (pinfunction "(SDA/INT1)PD1_44") (pintype "bidirectional"))
      (node (ref "JP4") (pin "3") (pinfunction "3_3") (pintype "passive"))
      (node (ref "PWMH") (pin "9") (pinfunction "9_9") (pintype "passive"))
      (node (ref "SJ5") (pin "1") (pinfunction "1_1") (pintype "passive"))
    )
    (net (code "94") (name "/SPDLED") (class "Default")
      (node (ref "IC6") (pin "24") (pinfunction "SPDLED_24") (pintype "passive"))
      (node (ref "RN9") (pin "4") (pinfunction "1_4") (pintype "passive"))
    )
    (net (code "95") (name "/TXD1") (class "Default")
      (node (ref "COMMUNICATION1") (pin "4") (pinfunction "4_4") (pintype "passive"))
      (node (ref "IC9") (pin "46") (pinfunction "(TXD1/INT3)PD3_46") (pintype "bidirectional"))
    )
    (net (code "96") (name "/TXD2") (class "Default")
      (node (ref "COMMUNICATION1") (pin "6") (pinfunction "6_6") (pintype "passive"))
      (node (ref "IC9") (pin "13") (pinfunction "PH1(TXD2)_13") (pintype "bidirectional"))
    )
    (net (code "97") (name "/TXD3") (class "Default")
      (node (ref "COMMUNICATION1") (pin "8") (pinfunction "8_8") (pintype "passive"))
      (node (ref "IC9") (pin "64") (pinfunction "PJ1(TXD3/PCINT10)_64") (pintype "bidirectional"))
    )
    (net (code "98") (name "/TXLED") (class "Default")
      (node (ref "IC3") (pin "11") (pinfunction "(XCK)PD5_11") (pintype "bidirectional"))
      (node (ref "RN3") (pin "8") (pinfunction "2_8") (pintype "passive"))
    )
    (net (code "99") (name "/TXON") (class "Default")
      (node (ref "IC6") (pin "1") (pinfunction "TXN_1") (pintype "passive"))
      (node (ref "RN5") (pin "4") (pinfunction "1_4") (pintype "passive"))
      (node (ref "U1") (pin "P$6") (pinfunction "TX-_P$6") (pintype "bidirectional"))
    )
    (net (code "100") (name "/TXOP") (class "Default")
      (node (ref "IC6") (pin "2") (pinfunction "TXP_2") (pintype "passive"))
      (node (ref "RN5") (pin "3") (pinfunction "1_3") (pintype "passive"))
      (node (ref "U1") (pin "P$5") (pinfunction "TX+_P$5") (pintype "bidirectional"))
    )
    (net (code "101") (name "/USB+") (class "Default")
      (node (ref "F1") (pin "1") (pinfunction "1_1") (pintype "passive"))
      (node (ref "U$15") (pin "A4") (pinfunction "V+_A4") (pintype "power_in"))
      (node (ref "U$15") (pin "A9") (pinfunction "V+_A9") (pintype "power_in"))
      (node (ref "U$15") (pin "B4") (pinfunction "V+_B4") (pintype "power_in"))
      (node (ref "U$15") (pin "B9") (pinfunction "V+_B9") (pintype "power_in"))
    )
    (net (code "102") (name "/USBRXD") (class "Default")
      (node (ref "IC3") (pin "9") (pinfunction "(TXD1)PD3_9") (pintype "bidirectional"))
      (node (ref "RN3") (pin "5") (pinfunction "2_5") (pintype "passive"))
    )
    (net (code "103") (name "/USBTXD") (class "Default")
      (node (ref "IC3") (pin "8") (pinfunction "(RXD1)PD2_8") (pintype "bidirectional"))
      (node (ref "RN3") (pin "6") (pinfunction "2_6") (pintype "passive"))
    )
    (net (code "104") (name "/USBVCC") (class "Default")
      (node (ref "F1") (pin "2") (pinfunction "2_2") (pintype "passive"))
      (node (ref "IC3") (pin "31") (pinfunction "UVCC_31") (pintype "power_in"))
      (node (ref "JP5") (pin "1") (pinfunction "1_1") (pintype "passive"))
    )
    (net (code "105") (name "/VIN") (class "Default")
      (node (ref "C36") (pin "1") (pinfunction "1_1") (pintype "passive"))
      (node (ref "D1") (pin "C") (pinfunction "C_C") (pintype "passive"))
      (node (ref "IC1") (pin "2") (pinfunction "IN_2") (pintype "power_in"))
      (node (ref "JP3") (pin "4") (pinfunction "VIN[4]_4") (pintype "passive"))
      (node (ref "JP6") (pin "1") (pinfunction "1_1") (pintype "passive"))
      (node (ref "R10") (pin "1") (pinfunction "1_1") (pintype "passive"))
    )
    (net (code "106") (name "/WIZRST") (class "Default")
      (node (ref "IC2") (pin "2") (pinfunction "/RESET_2") (pintype "output"))
      (node (ref "IC6") (pin "37") (pinfunction "RST_N_37") (pintype "passive"))
      (node (ref "RN2") (pin "2") (pinfunction "1_2") (pintype "passive"))
    )
    (net (code "107") (name "/XTAL1") (class "Default")
      (node (ref "C21") (pin "2") (pinfunction "2_2") (pintype "passive"))
      (node (ref "IC9") (pin "34") (pinfunction "XTAL1_34") (pintype "input"))
      (node (ref "R7") (pin "1") (pinfunction "1_1") (pintype "passive"))
      (node (ref "X3") (pin "1") (pinfunction "1_1") (pintype "passive"))
    )
    (net (code "108") (name "/XTAL2") (class "Default")
      (node (ref "C20") (pin "2") (pinfunction "2_2") (pintype "passive"))
      (node (ref "IC9") (pin "33") (pinfunction "XTAL2_33") (pintype "output"))
      (node (ref "R7") (pin "2") (pinfunction "2_2") (pintype "passive"))
      (node (ref "X3") (pin "2") (pinfunction "2_2") (pintype "passive"))
    )
    (net (code "109") (name "/XTLN") (class "Default")
      (node (ref "C15") (pin "1") (pinfunction "1_1") (pintype "passive"))
      (node (ref "IC6") (pin "31") (pinfunction "XO_31") (pintype "passive"))
      (node (ref "R3") (pin "1") (pinfunction "1_1") (pintype "passive"))
      (node (ref "X2") (pin "1") (pinfunction "1_1") (pintype "passive"))
    )
    (net (code "110") (name "/XTLP") (class "Default")
      (node (ref "C16") (pin "1") (pinfunction "1_1") (pintype "passive"))
      (node (ref "IC6") (pin "30") (pinfunction "XI/CLKIN_30") (pintype "passive"))
      (node (ref "R3") (pin "2") (pinfunction "2_2") (pintype "passive"))
      (node (ref "X2") (pin "2") (pinfunction "2_2") (pintype "passive"))
    )
    (net (code "111") (name "3.3V") (class "Default")
      (node (ref "C10") (pin "A") (pinfunction "+_A") (pintype "passive"))
      (node (ref "JP6") (pin "5") (pinfunction "5_5") (pintype "passive"))
      (node (ref "L1") (pin "1") (pinfunction "1_1") (pintype "passive"))
      (node (ref "L2") (pin "1") (pinfunction "1_1") (pintype "passive"))
      (node (ref "LED7") (pin "A") (pinfunction "A_A") (pintype "passive"))
      (node (ref "LED8") (pin "A") (pinfunction "A_A") (pintype "passive"))
      (node (ref "REG1") (pin "2") (pinfunction "OUT_2") (pintype "output"))
      (node (ref "REG1") (pin "4") (pinfunction "OUT_4") (pintype "output"))
      (node (ref "REG2") (pin "2") (pinfunction "OUT_2") (pintype "output"))
      (node (ref "REG2") (pin "4") (pinfunction "OUT_4") (pintype "output"))
      (node (ref "U1") (pin "P$11") (pinfunction "Y+_P$11") (pintype "bidirectional"))
      (node (ref "U1") (pin "P$13") (pinfunction "G+_P$13") (pintype "bidirectional"))
    )
    (net (code "112") (name "5V") (class "Default")
      (node (ref "C12") (pin "1") (pinfunction "1_1") (pintype "passive"))
      (node (ref "C31") (pin "1") (pinfunction "1_1") (pintype "passive"))
      (node (ref "C33") (pin "1") (pinfunction "1_1") (pintype "passive"))
      (node (ref "C34") (pin "1") (pinfunction "1_1") (pintype "passive"))
      (node (ref "C6") (pin "2") (pinfunction "2_2") (pintype "passive"))
      (node (ref "C7") (pin "1") (pinfunction "1_1") (pintype "passive"))
      (node (ref "C9") (pin "1") (pinfunction "1_1") (pintype "passive"))
      (node (ref "IC2") (pin "4") (pinfunction "VCC_4") (pintype "power_in"))
      (node (ref "IC3") (pin "32") (pinfunction "AVCC_32") (pintype "power_in"))
      (node (ref "IC3") (pin "4") (pinfunction "VCC_4") (pintype "power_in"))
      (node (ref "IC4") (pin "6") (pinfunction "VCC_6") (pintype "power_in"))
      (node (ref "IC9") (pin "10") (pinfunction "VCC_10") (pintype "power_in"))
      (node (ref "IC9") (pin "100") (pinfunction "AVCC_100") (pintype "power_in"))
      (node (ref "IC9") (pin "31") (pinfunction "VCC1_31") (pintype "power_in"))
      (node (ref "IC9") (pin "61") (pinfunction "VCC2_61") (pintype "power_in"))
      (node (ref "IC9") (pin "80") (pinfunction "VCC3_80") (pintype "power_in"))
      (node (ref "ICSP") (pin "2") (pinfunction "2_2") (pintype "passive"))
      (node (ref "JP1") (pin "1") (pinfunction "1_1") (pintype "passive"))
      (node (ref "JP1") (pin "2") (pinfunction "2_2") (pintype "passive"))
      (node (ref "JP4") (pin "1") (pinfunction "1_1") (pintype "passive"))
      (node (ref "JP5") (pin "2") (pinfunction "2_2") (pintype "passive"))
      (node (ref "JP6") (pin "4") (pinfunction "4_4") (pintype "passive"))
      (node (ref "JP6") (pin "7") (pinfunction "7_7") (pintype "passive"))
      (node (ref "LED10") (pin "A") (pinfunction "A_A") (pintype "passive"))
      (node (ref "LED2") (pin "A") (pinfunction "A_A") (pintype "passive"))
      (node (ref "LED5") (pin "A") (pinfunction "A_A") (pintype "passive"))
      (node (ref "LED6") (pin "A") (pinfunction "A_A") (pintype "passive"))
      (node (ref "P3") (pin "2") (pinfunction "2_2") (pintype "passive"))
      (node (ref "R14") (pin "1") (pinfunction "1_1") (pintype "passive"))
      (node (ref "R15") (pin "1") (pinfunction "1_1") (pintype "passive"))
      (node (ref "R16") (pin "2") (pinfunction "2_2") (pintype "passive"))
      (node (ref "R17") (pin "2") (pinfunction "2_2") (pintype "passive"))
      (node (ref "REG1") (pin "3") (pinfunction "IN_3") (pintype "input"))
      (node (ref "REG2") (pin "3") (pinfunction "IN_3") (pintype "input"))
    )
    (net (code "113") (name "GND") (class "Default")
      (node (ref "C1") (pin "2") (pinfunction "2_2") (pintype "passive"))
      (node (ref "C10") (pin "C") (pinfunction "-_C") (pintype "passive"))
      (node (ref "C11") (pin "2") (pinfunction "2_2") (pintype "passive"))
      (node (ref "C12") (pin "2") (pinfunction "2_2") (pintype "passive"))
      (node (ref "C13") (pin "C") (pinfunction "-_C") (pintype "passive"))
      (node (ref "C14") (pin "2") (pinfunction "2_2") (pintype "passive"))
      (node (ref "C15") (pin "2") (pinfunction "2_2") (pintype "passive"))
      (node (ref "C16") (pin "2") (pinfunction "2_2") (pintype "passive"))
      (node (ref "C17") (pin "2") (pinfunction "2_2") (pintype "passive"))
      (node (ref "C2") (pin "1") (pinfunction "1_1") (pintype "passive"))
      (node (ref "C20") (pin "1") (pinfunction "1_1") (pintype "passive"))
      (node (ref "C21") (pin "1") (pinfunction "1_1") (pintype "passive"))
      (node (ref "C22") (pin "2") (pinfunction "2_2") (pintype "passive"))
      (node (ref "C23") (pin "2") (pinfunction "2_2") (pintype "passive"))
      (node (ref "C24") (pin "2") (pinfunction "2_2") (pintype "passive"))
      (node (ref "C27") (pin "2") (pinfunction "2_2") (pintype "passive"))
      (node (ref "C29") (pin "2") (pinfunction "2_2") (pintype "passive"))
      (node (ref "C3") (pin "C") (pinfunction "-_C") (pintype "passive"))
      (node (ref "C30") (pin "2") (pinfunction "2_2") (pintype "passive"))
      (node (ref "C31") (pin "2") (pinfunction "2_2") (pintype "passive"))
      (node (ref "C33") (pin "2") (pinfunction "2_2") (pintype "passive"))
      (node (ref "C34") (pin "2") (pinfunction "2_2") (pintype "passive"))
      (node (ref "C35") (pin "2") (pinfunction "2_2") (pintype "passive"))
      (node (ref "C36") (pin "2") (pinfunction "2_2") (pintype "passive"))
      (node (ref "C37") (pin "2") (pinfunction "2_2") (pintype "passive"))
      (node (ref "C4") (pin "C") (pinfunction "-_C") (pintype "passive"))
      (node (ref "C5") (pin "2") (pinfunction "2_2") (pintype "passive"))
      (node (ref "C6") (pin "1") (pinfunction "1_1") (pintype "passive"))
      (node (ref "C7") (pin "2") (pinfunction "2_2") (pintype "passive"))
      (node (ref "C8") (pin "1") (pinfunction "1_1") (pintype "passive"))
      (node (ref "C9") (pin "2") (pinfunction "2_2") (pintype "passive"))
      (node (ref "IC1") (pin "4") (pinfunction "GND_4") (pintype "power_in"))
      (node (ref "IC1") (pin "9") (pinfunction "TGND_9") (pintype "power_in"))
      (node (ref "IC2") (pin "1") (pinfunction "GND_1") (pintype "power_in"))
      (node (ref "IC3") (pin "28") (pinfunction "UGND_28") (pintype "power_in"))
      (node (ref "IC3") (pin "3") (pinfunction "GND_3") (pintype "power_in"))
      (node (ref "IC3") (pin "EXP") (pinfunction "PAD_EXP") (pintype "power_in"))
      (node (ref "IC4") (pin "2") (pinfunction "GND_2") (pintype "power_in"))
      (node (ref "IC4") (pin "4") (pinfunction "A1_4") (pintype "input"))
      (node (ref "IC4") (pin "5") (pinfunction "A0_5") (pintype "input"))
      (node (ref "IC6") (pin "14") (pinfunction "AGND_14") (pintype "passive"))
      (node (ref "IC6") (pin "16") (pinfunction "AGND_16") (pintype "passive"))
      (node (ref "IC6") (pin "19") (pinfunction "AGND_19") (pintype "passive"))
      (node (ref "IC6") (pin "29") (pinfunction "GND_29") (pintype "passive"))
      (node (ref "IC6") (pin "3") (pinfunction "AGND_3") (pintype "passive"))
      (node (ref "IC6") (pin "48") (pinfunction "AGND_48") (pintype "passive"))
      (node (ref "IC6") (pin "9") (pinfunction "AGND_9") (pintype "passive"))
      (node (ref "IC9") (pin "11") (pinfunction "GND_11") (pintype "power_in"))
      (node (ref "IC9") (pin "32") (pinfunction "GND1_32") (pintype "power_in"))
      (node (ref "IC9") (pin "62") (pinfunction "GND2_62") (pintype "power_in"))
      (node (ref "IC9") (pin "81") (pinfunction "GND3_81") (pintype "power_in"))
      (node (ref "IC9") (pin "99") (pinfunction "AGND_99") (pintype "power_in"))
      (node (ref "ICSP") (pin "6") (pinfunction "6_6") (pintype "passive"))
      (node (ref "J1") (pin "GND") (pinfunction "GND_GND") (pintype "bidirectional"))
      (node (ref "J1") (pin "GNDBREAK") (pinfunction "GNDBREAK_GNDBREAK") (pintype "bidirectional"))
      (node (ref "JP2") (pin "1") (pinfunction "1_1") (pintype "passive"))
      (node (ref "JP2") (pin "2") (pinfunction "2_2") (pintype "passive"))
      (node (ref "JP3") (pin "1") (pinfunction "GND[1]_1") (pintype "passive"))
      (node (ref "JP3") (pin "MNT1") (pinfunction "MNT1_MNT1") (pintype "passive"))
      (node (ref "JP3") (pin "MNT2") (pinfunction "MNT2_MNT2") (pintype "passive"))
      (node (ref "JP4") (pin "4") (pinfunction "4_4") (pintype "passive"))
      (node (ref "JP6") (pin "2") (pinfunction "2_2") (pintype "passive"))
      (node (ref "JP6") (pin "3") (pinfunction "3_3") (pintype "passive"))
      (node (ref "P3") (pin "6") (pinfunction "6_6") (pintype "passive"))
      (node (ref "P4") (pin "6") (pinfunction "GND_6") (pintype "bidirectional"))
      (node (ref "P4") (pin "GND1") (pinfunction "SHIELD1_GND1") (pintype "bidirectional"))
      (node (ref "P4") (pin "GND2") (pinfunction "SHIELD2_GND2") (pintype "bidirectional"))
      (node (ref "P4") (pin "GND3") (pinfunction "CD1_GND3") (pintype "bidirectional"))
      (node (ref "P4") (pin "GND4") (pinfunction "CD2_GND4") (pintype "bidirectional"))
      (node (ref "PWMH") (pin "7") (pinfunction "7_7") (pintype "passive"))
      (node (ref "Q2") (pin "2") (pinfunction "S_2") (pintype "passive"))
      (node (ref "R11") (pin "1") (pinfunction "1_1") (pintype "passive"))
      (node (ref "R13") (pin "1") (pinfunction "1_1") (pintype "passive"))
      (node (ref "R18") (pin "1") (pinfunction "1_1") (pintype "passive"))
      (node (ref "R22") (pin "1") (pinfunction "1_1") (pintype "passive"))
      (node (ref "R6") (pin "1") (pinfunction "1_1") (pintype "passive"))
      (node (ref "REG1") (pin "1") (pinfunction "ADJ_1") (pintype "input"))
      (node (ref "REG2") (pin "1") (pinfunction "ADJ_1") (pintype "input"))
      (node (ref "RN1") (pin "5") (pinfunction "2_5") (pintype "passive"))
      (node (ref "RN1") (pin "6") (pinfunction "2_6") (pintype "passive"))
      (node (ref "RN1") (pin "7") (pinfunction "2_7") (pintype "passive"))
      (node (ref "RN1") (pin "8") (pinfunction "2_8") (pintype "passive"))
      (node (ref "RN2") (pin "8") (pinfunction "2_8") (pintype "passive"))
      (node (ref "RN8") (pin "1") (pinfunction "1_1") (pintype "passive"))
      (node (ref "RN8") (pin "2") (pinfunction "1_2") (pintype "passive"))
      (node (ref "RN8") (pin "3") (pinfunction "1_3") (pintype "passive"))
      (node (ref "S1") (pin "1") (pinfunction "1_1") (pintype "passive"))
      (node (ref "S1") (pin "2") (pinfunction "2_2") (pintype "passive"))
      (node (ref "SJ2") (pin "1") (pinfunction "1_1") (pintype "passive"))
      (node (ref "U$15") (pin "A1") (pinfunction "GND_A1") (pintype "power_in"))
      (node (ref "U$15") (pin "A12") (pinfunction "GND_A12") (pintype "power_in"))
      (node (ref "U$15") (pin "B1") (pinfunction "GND_B1") (pintype "power_in"))
      (node (ref "U$15") (pin "B12") (pinfunction "GND_B12") (pintype "power_in"))
      (node (ref "U$15") (pin "CASE1") (pinfunction "GND_CASE1") (pintype "power_in"))
      (node (ref "U$15") (pin "CASE2") (pinfunction "GND_CASE2") (pintype "power_in"))
      (node (ref "U$15") (pin "CASE3") (pinfunction "GND_CASE3") (pintype "power_in"))
      (node (ref "U$15") (pin "CASE4") (pinfunction "GND_CASE4") (pintype "power_in"))
      (node (ref "U$15") (pin "FIX1") (pinfunction "GND_FIX1") (pintype "power_in"))
      (node (ref "U$15") (pin "FIX2") (pinfunction "GND_FIX2") (pintype "power_in"))
      (node (ref "U$15") (pin "FIX3") (pinfunction "GND_FIX3") (pintype "power_in"))
      (node (ref "U$15") (pin "FIX4") (pinfunction "GND_FIX4") (pintype "power_in"))
      (node (ref "U1") (pin "GND1") (pinfunction "GND1_GND1") (pintype "bidirectional"))
      (node (ref "U1") (pin "GND2") (pinfunction "GND2_GND2") (pintype "bidirectional"))
      (node (ref "Z1") (pin "2") (pinfunction "2_2") (pintype "passive"))
      (node (ref "Z2") (pin "2") (pinfunction "2_2") (pintype "passive"))
    )
    (net (code "114") (name "Net-(C1-Pad1)") (class "Default")
      (node (ref "C1") (pin "1") (pinfunction "1_1") (pintype "passive"))
      (node (ref "R9") (pin "1") (pinfunction "1_1") (pintype "passive"))
    )
    (net (code "115") (name "Net-(C3-+)") (class "Default")
      (node (ref "C3") (pin "A") (pinfunction "+_A") (pintype "passive"))
      (node (ref "IC6") (pin "20") (pinfunction "TOCAP_20") (pintype "passive"))
    )
    (net (code "116") (name "Net-(C8-Pad2)") (class "Default")
      (node (ref "C8") (pin "2") (pinfunction "2_2") (pintype "passive"))
      (node (ref "R1") (pin "1") (pinfunction "1_1") (pintype "passive"))
      (node (ref "R2") (pin "2") (pinfunction "2_2") (pintype "passive"))
      (node (ref "X1") (pin "1") (pinfunction "1_1") (pintype "passive"))
    )
    (net (code "117") (name "Net-(C19-Pad1)") (class "Default")
      (node (ref "C19") (pin "1") (pinfunction "1_1") (pintype "passive"))
      (node (ref "JP7") (pin "1") (pinfunction "1_1") (pintype "passive"))
      (node (ref "SJ3") (pin "2") (pinfunction "2_2") (pintype "passive"))
    )
    (net (code "118") (name "Net-(D1-PadA)") (class "Default")
      (node (ref "D1") (pin "A") (pinfunction "A_A") (pintype "passive"))
      (node (ref "J1") (pin "PWR") (pinfunction "PWR_PWR") (pintype "bidirectional"))
    )
    (net (code "119") (name "Net-(IC1-BS)") (class "Default")
      (node (ref "C32") (pin "2") (pinfunction "2_2") (pintype "passive"))
      (node (ref "IC1") (pin "1") (pinfunction "BS_1") (pintype "bidirectional"))
    )
    (net (code "120") (name "Net-(IC1-COMP)") (class "Default")
      (node (ref "C35") (pin "1") (pinfunction "1_1") (pintype "passive"))
      (node (ref "IC1") (pin "6") (pinfunction "COMP_6") (pintype "bidirectional"))
      (node (ref "R9") (pin "2") (pinfunction "2_2") (pintype "passive"))
    )
    (net (code "121") (name "Net-(IC1-EN)") (class "Default")
      (node (ref "IC1") (pin "7") (pinfunction "EN_7") (pintype "input"))
      (node (ref "R10") (pin "2") (pinfunction "2_2") (pintype "passive"))
    )
    (net (code "122") (name "Net-(IC1-FB)") (class "Default")
      (node (ref "IC1") (pin "5") (pinfunction "FB_5") (pintype "bidirectional"))
      (node (ref "R11") (pin "2") (pinfunction "2_2") (pintype "passive"))
      (node (ref "R12") (pin "1") (pinfunction "1_1") (pintype "passive"))
    )
    (net (code "123") (name "Net-(IC1-SS)") (class "Default")
      (node (ref "C27") (pin "1") (pinfunction "1_1") (pintype "passive"))
      (node (ref "IC1") (pin "8") (pinfunction "SS_8") (pintype "bidirectional"))
    )
    (net (code "124") (name "Net-(IC1-SW)") (class "Default")
      (node (ref "C32") (pin "1") (pinfunction "1_1") (pintype "passive"))
      (node (ref "IC1") (pin "3") (pinfunction "SW_3") (pintype "bidirectional"))
      (node (ref "L4") (pin "1") (pinfunction "1_1") (pintype "bidirectional"))
    )
    (net (code "125") (name "Net-(IC3-UCAP)") (class "Default")
      (node (ref "C11") (pin "1") (pinfunction "1_1") (pintype "passive"))
      (node (ref "IC3") (pin "27") (pinfunction "UCAP_27") (pintype "passive"))
    )
    (net (code "126") (name "Net-(IC3-XTAL1)") (class "Default")
      (node (ref "IC3") (pin "1") (pinfunction "XTAL1_1") (pintype "bidirectional"))
      (node (ref "R2") (pin "1") (pinfunction "1_1") (pintype "passive"))
    )
    (net (code "127") (name "Net-(IC3-XTAL2)") (class "Default")
      (node (ref "C2") (pin "2") (pinfunction "2_2") (pintype "passive"))
      (node (ref "IC3") (pin "2") (pinfunction "XTAL2_2") (pintype "bidirectional"))
      (node (ref "R1") (pin "2") (pinfunction "2_2") (pintype "passive"))
      (node (ref "X1") (pin "2") (pinfunction "2_2") (pintype "passive"))
    )
    (net (code "128") (name "Net-(IC4-SCL)") (class "Default")
      (node (ref "IC4") (pin "1") (pinfunction "SCL_1") (pintype "bidirectional"))
      (node (ref "R15") (pin "2") (pinfunction "2_2") (pintype "passive"))
      (node (ref "SJ6") (pin "2") (pinfunction "2_2") (pintype "passive"))
    )
    (net (code "129") (name "Net-(IC4-SDA)") (class "Default")
      (node (ref "IC4") (pin "3") (pinfunction "SDA_3") (pintype "bidirectional"))
      (node (ref "R14") (pin "2") (pinfunction "2_2") (pintype "passive"))
      (node (ref "SJ5") (pin "2") (pinfunction "2_2") (pintype "passive"))
    )
    (net (code "130") (name "Net-(IC6-1V2O)") (class "Default")
      (node (ref "C5") (pin "1") (pinfunction "1_1") (pintype "passive"))
      (node (ref "IC6") (pin "22") (pinfunction "1V2O_22") (pintype "passive"))
    )
    (net (code "131") (name "Net-(IC6-RSVD-Pad23)") (class "Default")
      (node (ref "IC6") (pin "23") (pinfunction "RSVD_23") (pintype "passive"))
      (node (ref "R22") (pin "2") (pinfunction "2_2") (pintype "passive"))
    )
    (net (code "132") (name "Net-(IC6-RSVD-Pad38)") (class "Default")
      (node (ref "IC6") (pin "38") (pinfunction "RSVD_38") (pintype "passive"))
      (node (ref "RN2") (pin "1") (pinfunction "1_1") (pintype "passive"))
    )
    (net (code "133") (name "Net-(IC6-RSVD-Pad42)") (class "Default")
      (node (ref "IC6") (pin "42") (pinfunction "RSVD_42") (pintype "passive"))
      (node (ref "RN1") (pin "1") (pinfunction "1_1") (pintype "passive"))
    )
    (net (code "134") (name "Net-(JP3-V+[3])") (class "Default")
      (node (ref "JP3") (pin "3") (pinfunction "V+[3]_3") (pintype "passive"))
      (node (ref "U1") (pin "P$9") (pinfunction "V+_P$9") (pintype "bidirectional"))
    )
    (net (code "135") (name "Net-(JP3-V-[2])") (class "Default")
      (node (ref "JP3") (pin "2") (pinfunction "V-[2]_2") (pintype "passive"))
      (node (ref "U1") (pin "P$10") (pinfunction "V-_P$10") (pintype "bidirectional"))
    )
    (net (code "136") (name "Net-(LED2-PadC)") (class "Default")
      (node (ref "LED2") (pin "C") (pinfunction "C_C") (pintype "passive"))
      (node (ref "R13") (pin "2") (pinfunction "2_2") (pintype "passive"))
    )
    (net (code "137") (name "Net-(LED5-PadC)") (class "Default")
      (node (ref "LED5") (pin "C") (pinfunction "C_C") (pintype "passive"))
      (node (ref "RN3") (pin "1") (pinfunction "1_1") (pintype "passive"))
    )
    (net (code "138") (name "Net-(LED10-PadC)") (class "Default")
      (node (ref "LED10") (pin "C") (pinfunction "C_C") (pintype "passive"))
      (node (ref "R8") (pin "2") (pinfunction "2_2") (pintype "passive"))
    )
    (net (code "139") (name "Net-(P4-CS)") (class "Default")
      (node (ref "P4") (pin "2") (pinfunction "CS_2") (pintype "bidirectional"))
      (node (ref "RN6") (pin "2") (pinfunction "1_2") (pintype "passive"))
      (node (ref "RN8") (pin "8") (pinfunction "2_8") (pintype "passive"))
    )
    (net (code "140") (name "Net-(P4-DI)") (class "Default")
      (node (ref "P4") (pin "3") (pinfunction "DI_3") (pintype "bidirectional"))
      (node (ref "RN6") (pin "3") (pinfunction "1_3") (pintype "passive"))
      (node (ref "RN8") (pin "7") (pinfunction "2_7") (pintype "passive"))
    )
    (net (code "141") (name "Net-(P4-SCK)") (class "Default")
      (node (ref "P4") (pin "5") (pinfunction "SCK_5") (pintype "bidirectional"))
      (node (ref "RN6") (pin "4") (pinfunction "1_4") (pintype "passive"))
      (node (ref "RN8") (pin "6") (pinfunction "2_6") (pintype "passive"))
    )
    (net (code "142") (name "Net-(Q2-D)") (class "Default")
      (node (ref "Q2") (pin "3") (pinfunction "D_3") (pintype "passive"))
      (node (ref "R8") (pin "1") (pinfunction "1_1") (pintype "passive"))
    )
    (net (code "143") (name "Net-(RN1B-1)") (class "Default")
      (node (ref "IC6") (pin "41") (pinfunction "RSVD_41") (pintype "passive"))
      (node (ref "RN1") (pin "2") (pinfunction "1_2") (pintype "passive"))
    )
    (net (code "144") (name "Net-(RN1C-1)") (class "Default")
      (node (ref "IC6") (pin "40") (pinfunction "RSVD_40") (pintype "passive"))
      (node (ref "RN1") (pin "3") (pinfunction "1_3") (pintype "passive"))
    )
    (net (code "145") (name "Net-(RN1D-1)") (class "Default")
      (node (ref "IC6") (pin "39") (pinfunction "RSVD_39") (pintype "passive"))
      (node (ref "RN1") (pin "4") (pinfunction "1_4") (pintype "passive"))
    )
    (net (code "146") (name "Net-(RN3B-1)") (class "Default")
      (node (ref "LED6") (pin "C") (pinfunction "C_C") (pintype "passive"))
      (node (ref "RN3") (pin "2") (pinfunction "1_2") (pintype "passive"))
    )
    (net (code "147") (name "Net-(RN5A-2)") (class "Default")
      (node (ref "C23") (pin "1") (pinfunction "1_1") (pintype "passive"))
      (node (ref "RN5") (pin "7") (pinfunction "2_7") (pintype "passive"))
      (node (ref "RN5") (pin "8") (pinfunction "2_8") (pintype "passive"))
    )
    (net (code "148") (name "Net-(RN5C-2)") (class "Default")
      (node (ref "C24") (pin "1") (pinfunction "1_1") (pintype "passive"))
      (node (ref "RN5") (pin "5") (pinfunction "2_5") (pintype "passive"))
      (node (ref "RN5") (pin "6") (pinfunction "2_6") (pintype "passive"))
    )
    (net (code "149") (name "Net-(RN9A-2)") (class "Default")
      (node (ref "RN9") (pin "8") (pinfunction "2_8") (pintype "passive"))
      (node (ref "U1") (pin "P$12") (pinfunction "Y-_P$12") (pintype "bidirectional"))
    )
    (net (code "150") (name "Net-(RN9B-2)") (class "Default")
      (node (ref "LED7") (pin "C") (pinfunction "C_C") (pintype "passive"))
      (node (ref "RN9") (pin "7") (pinfunction "2_7") (pintype "passive"))
    )
    (net (code "151") (name "Net-(RN9C-2)") (class "Default")
      (node (ref "RN9") (pin "6") (pinfunction "2_6") (pintype "passive"))
      (node (ref "U1") (pin "P$14") (pinfunction "G-_P$14") (pintype "bidirectional"))
    )
    (net (code "152") (name "Net-(RN9D-2)") (class "Default")
      (node (ref "LED8") (pin "C") (pinfunction "C_C") (pintype "passive"))
      (node (ref "RN9") (pin "5") (pinfunction "2_5") (pintype "passive"))
    )
    (net (code "153") (name "Net-(U$15-CC1)") (class "Default")
      (node (ref "R18") (pin "2") (pinfunction "2_2") (pintype "passive"))
      (node (ref "U$15") (pin "A5") (pinfunction "CC1_A5") (pintype "bidirectional"))
      (node (ref "U$15") (pin "B5") (pinfunction "CC2_B5") (pintype "bidirectional"))
    )
    (net (code "154") (name "unconnected-(IC3-(RTS)PD6-Pad12)") (class "Default")
      (node (ref "IC3") (pin "12") (pinfunction "(RTS)PD6_12") (pintype "bidirectional"))
    )
    (net (code "155") (name "unconnected-(IC3-(SS)PB0-Pad14)") (class "Default")
      (node (ref "IC3") (pin "14") (pinfunction "(SS)PB0_14") (pintype "bidirectional"))
    )
    (net (code "156") (name "unconnected-(IC3-PB4-Pad18)") (class "Default")
      (node (ref "IC3") (pin "18") (pinfunction "PB4_18") (pintype "bidirectional"))
    )
    (net (code "157") (name "unconnected-(IC3-PB5-Pad19)") (class "Default")
      (node (ref "IC3") (pin "19") (pinfunction "PB5_19") (pintype "bidirectional"))
    )
    (net (code "158") (name "unconnected-(IC3-PB6-Pad20)") (class "Default")
      (node (ref "IC3") (pin "20") (pinfunction "PB6_20") (pintype "bidirectional"))
    )
    (net (code "159") (name "unconnected-(IC3-PB7-Pad21)") (class "Default")
      (node (ref "IC3") (pin "21") (pinfunction "PB7_21") (pintype "bidirectional"))
    )
    (net (code "160") (name "unconnected-(IC3-PC2-Pad5)") (class "Default")
      (node (ref "IC3") (pin "5") (pinfunction "PC2_5") (pintype "bidirectional"))
    )
    (net (code "161") (name "unconnected-(IC3-PC4-Pad26)") (class "Default")
      (node (ref "IC3") (pin "26") (pinfunction "PC4_26") (pintype "bidirectional"))
    )
    (net (code "162") (name "unconnected-(IC3-PC5-Pad25)") (class "Default")
      (node (ref "IC3") (pin "25") (pinfunction "PC5_25") (pintype "bidirectional"))
    )
    (net (code "163") (name "unconnected-(IC3-PC6-Pad23)") (class "Default")
      (node (ref "IC3") (pin "23") (pinfunction "PC6_23") (pintype "bidirectional"))
    )
    (net (code "164") (name "unconnected-(IC3-PC7-Pad22)") (class "Default")
      (node (ref "IC3") (pin "22") (pinfunction "PC7_22") (pintype "bidirectional"))
    )
    (net (code "165") (name "unconnected-(IC3-PD0-Pad6)") (class "Default")
      (node (ref "IC3") (pin "6") (pinfunction "PD0_6") (pintype "bidirectional"))
    )
    (net (code "166") (name "unconnected-(IC3-PD1-Pad7)") (class "Default")
      (node (ref "IC3") (pin "7") (pinfunction "PD1_7") (pintype "bidirectional"))
    )
    (net (code "167") (name "unconnected-(IC6-DNC-Pad7)") (class "Default")
      (node (ref "IC6") (pin "7") (pinfunction "DNC_7") (pintype "passive"))
    )
    (net (code "168") (name "unconnected-(IC6-NC-Pad12)") (class "Default")
      (node (ref "IC6") (pin "12") (pinfunction "NC_12") (pintype "passive"))
    )
    (net (code "169") (name "unconnected-(IC6-NC-Pad13)") (class "Default")
      (node (ref "IC6") (pin "13") (pinfunction "NC_13") (pintype "passive"))
    )
    (net (code "170") (name "unconnected-(IC6-NC-Pad46)") (class "Default")
      (node (ref "IC6") (pin "46") (pinfunction "NC_46") (pintype "passive"))
    )
    (net (code "171") (name "unconnected-(IC6-NC-Pad47)") (class "Default")
      (node (ref "IC6") (pin "47") (pinfunction "NC_47") (pintype "passive"))
    )
    (net (code "172") (name "unconnected-(IC6-VBG-Pad18)") (class "Default")
      (node (ref "IC6") (pin "18") (pinfunction "VBG_18") (pintype "passive"))
    )
    (net (code "173") (name "unconnected-(IC9-(CLKO{slash}ICP3{slash}INT7)PE7-Pad9)") (class "Default")
      (node (ref "IC9") (pin "9") (pinfunction "(CLKO/ICP3/INT7)PE7_9") (pintype "bidirectional"))
    )
    (net (code "174") (name "unconnected-(IC9-(ICP1)PD4-Pad47)") (class "Default")
      (node (ref "IC9") (pin "47") (pinfunction "(ICP1)PD4_47") (pintype "bidirectional"))
    )
    (net (code "175") (name "unconnected-(IC9-(T1)PD6-Pad49)") (class "Default")
      (node (ref "IC9") (pin "49") (pinfunction "(T1)PD6_49") (pintype "bidirectional"))
    )
    (net (code "176") (name "unconnected-(IC9-(T3{slash}INT6)PE6-Pad8)") (class "Default")
      (node (ref "IC9") (pin "8") (pinfunction "(T3/INT6)PE6_8") (pintype "bidirectional"))
    )
    (net (code "177") (name "unconnected-(IC9-(TOSC1)PG4-Pad29)") (class "Default")
      (node (ref "IC9") (pin "29") (pinfunction "(TOSC1)PG4_29") (pintype "bidirectional"))
    )
    (net (code "178") (name "unconnected-(IC9-(TOSC2)PG3-Pad28)") (class "Default")
      (node (ref "IC9") (pin "28") (pinfunction "(TOSC2)PG3_28") (pintype "bidirectional"))
    )
    (net (code "179") (name "unconnected-(IC9-(XCK0{slash}AIN0)PE2-Pad4)") (class "Default")
      (node (ref "IC9") (pin "4") (pinfunction "(XCK0/AIN0)PE2_4") (pintype "bidirectional"))
    )
    (net (code "180") (name "unconnected-(IC9-(XCK1)PD5-Pad48)") (class "Default")
      (node (ref "IC9") (pin "48") (pinfunction "(XCK1)PD5_48") (pintype "bidirectional"))
    )
    (net (code "181") (name "unconnected-(IC9-PH2(XCK2)-Pad14)") (class "Default")
      (node (ref "IC9") (pin "14") (pinfunction "PH2(XCK2)_14") (pintype "bidirectional"))
    )
    (net (code "182") (name "unconnected-(IC9-PH7(T4)-Pad27)") (class "Default")
      (node (ref "IC9") (pin "27") (pinfunction "PH7(T4)_27") (pintype "bidirectional"))
    )
    (net (code "183") (name "unconnected-(IC9-PJ2(XCK3{slash}PCINT11)-Pad65)") (class "Default")
      (node (ref "IC9") (pin "65") (pinfunction "PJ2(XCK3/PCINT11)_65") (pintype "bidirectional"))
    )
    (net (code "184") (name "unconnected-(IC9-PJ3(PCINT12)-Pad66)") (class "Default")
      (node (ref "IC9") (pin "66") (pinfunction "PJ3(PCINT12)_66") (pintype "bidirectional"))
    )
    (net (code "185") (name "unconnected-(IC9-PJ4(PCINT13)-Pad67)") (class "Default")
      (node (ref "IC9") (pin "67") (pinfunction "PJ4(PCINT13)_67") (pintype "bidirectional"))
    )
    (net (code "186") (name "unconnected-(IC9-PJ5(PCINT14)-Pad68)") (class "Default")
      (node (ref "IC9") (pin "68") (pinfunction "PJ5(PCINT14)_68") (pintype "bidirectional"))
    )
    (net (code "187") (name "unconnected-(IC9-PJ6(PCINT15)-Pad69)") (class "Default")
      (node (ref "IC9") (pin "69") (pinfunction "PJ6(PCINT15)_69") (pintype "bidirectional"))
    )
    (net (code "188") (name "unconnected-(IC9-PJ7-Pad79)") (class "Default")
      (node (ref "IC9") (pin "79") (pinfunction "PJ7_79") (pintype "bidirectional"))
    )
    (net (code "189") (name "unconnected-(P4-NC-Pad1)") (class "Default")
      (node (ref "P4") (pin "1") (pinfunction "NC_1") (pintype "bidirectional"))
    )
    (net (code "190") (name "unconnected-(P4-RSV-Pad8)") (class "Default")
      (node (ref "P4") (pin "8") (pinfunction "RSV_8") (pintype "bidirectional"))
    )
    (net (code "191") (name "unconnected-(RN6-Pad1)") (class "Default")
      (node (ref "RN6") (pin "1") (pinfunction "1_1") (pintype "passive"))
    )
    (net (code "192") (name "unconnected-(RN6A-2-Pad8)") (class "Default")
      (node (ref "RN6") (pin "8") (pinfunction "2_8") (pintype "passive"))
    )
    (net (code "193") (name "unconnected-(RN8D-1-Pad4)") (class "Default")
      (node (ref "RN8") (pin "4") (pinfunction "1_4") (pintype "passive"))
    )
    (net (code "194") (name "unconnected-(RN8D-2-Pad5)") (class "Default")
      (node (ref "RN8") (pin "5") (pinfunction "2_5") (pintype "passive"))
    )
    (net (code "195") (name "unconnected-(U$15-RX1+-PadB11)") (class "Default")
      (node (ref "U$15") (pin "B11") (pinfunction "RX1+_B11") (pintype "bidirectional"))
    )
    (net (code "196") (name "unconnected-(U$15-RX1--PadB10)") (class "Default")
      (node (ref "U$15") (pin "B10") (pinfunction "RX1-_B10") (pintype "bidirectional"))
    )
    (net (code "197") (name "unconnected-(U$15-RX2+-PadA11)") (class "Default")
      (node (ref "U$15") (pin "A11") (pinfunction "RX2+_A11") (pintype "bidirectional"))
    )
    (net (code "198") (name "unconnected-(U$15-RX2--PadA10)") (class "Default")
      (node (ref "U$15") (pin "A10") (pinfunction "RX2-_A10") (pintype "bidirectional"))
    )
    (net (code "199") (name "unconnected-(U$15-SBU1-PadA8)") (class "Default")
      (node (ref "U$15") (pin "A8") (pinfunction "SBU1_A8") (pintype "bidirectional"))
    )
    (net (code "200") (name "unconnected-(U$15-SBU2-PadB8)") (class "Default")
      (node (ref "U$15") (pin "B8") (pinfunction "SBU2_B8") (pintype "bidirectional"))
    )
    (net (code "201") (name "unconnected-(U$15-TX1+-PadA2)") (class "Default")
      (node (ref "U$15") (pin "A2") (pinfunction "TX1+_A2") (pintype "bidirectional"))
    )
    (net (code "202") (name "unconnected-(U$15-TX1--PadA3)") (class "Default")
      (node (ref "U$15") (pin "A3") (pinfunction "TX1-_A3") (pintype "bidirectional"))
    )
    (net (code "203") (name "unconnected-(U$15-TX2+-PadB2)") (class "Default")
      (node (ref "U$15") (pin "B2") (pinfunction "TX2+_B2") (pintype "bidirectional"))
    )
    (net (code "204") (name "unconnected-(U$15-TX2--PadB3)") (class "Default")
      (node (ref "U$15") (pin "B3") (pinfunction "TX2-_B3") (pintype "bidirectional"))
    )
  )
)
